# LogicPCB.net
KiCad netlist of a schematic drawn in EAGLE
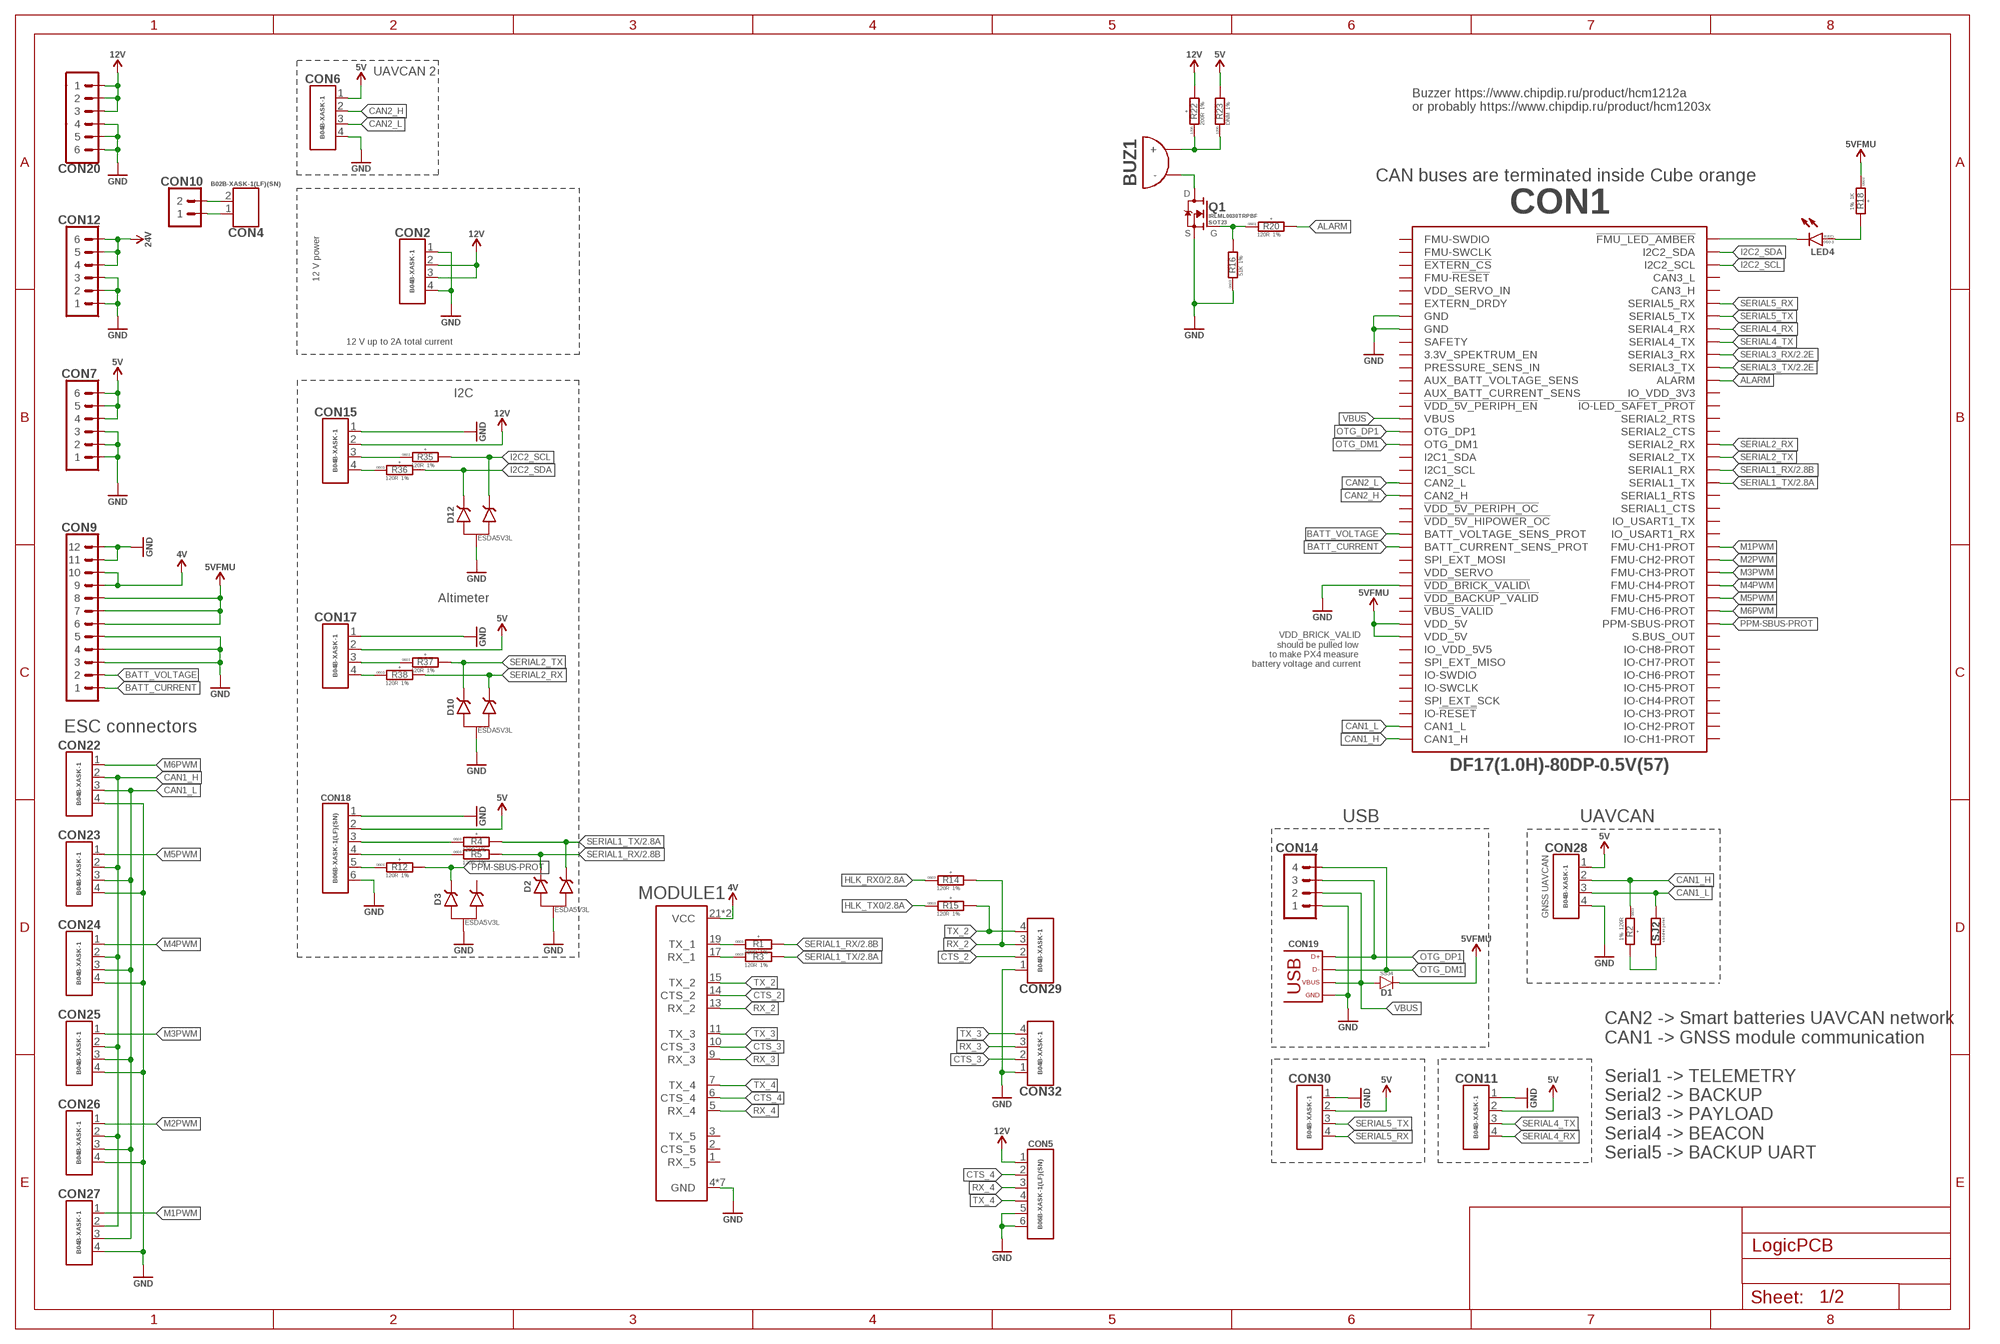
[diagram p0: schematic, sheet 1]
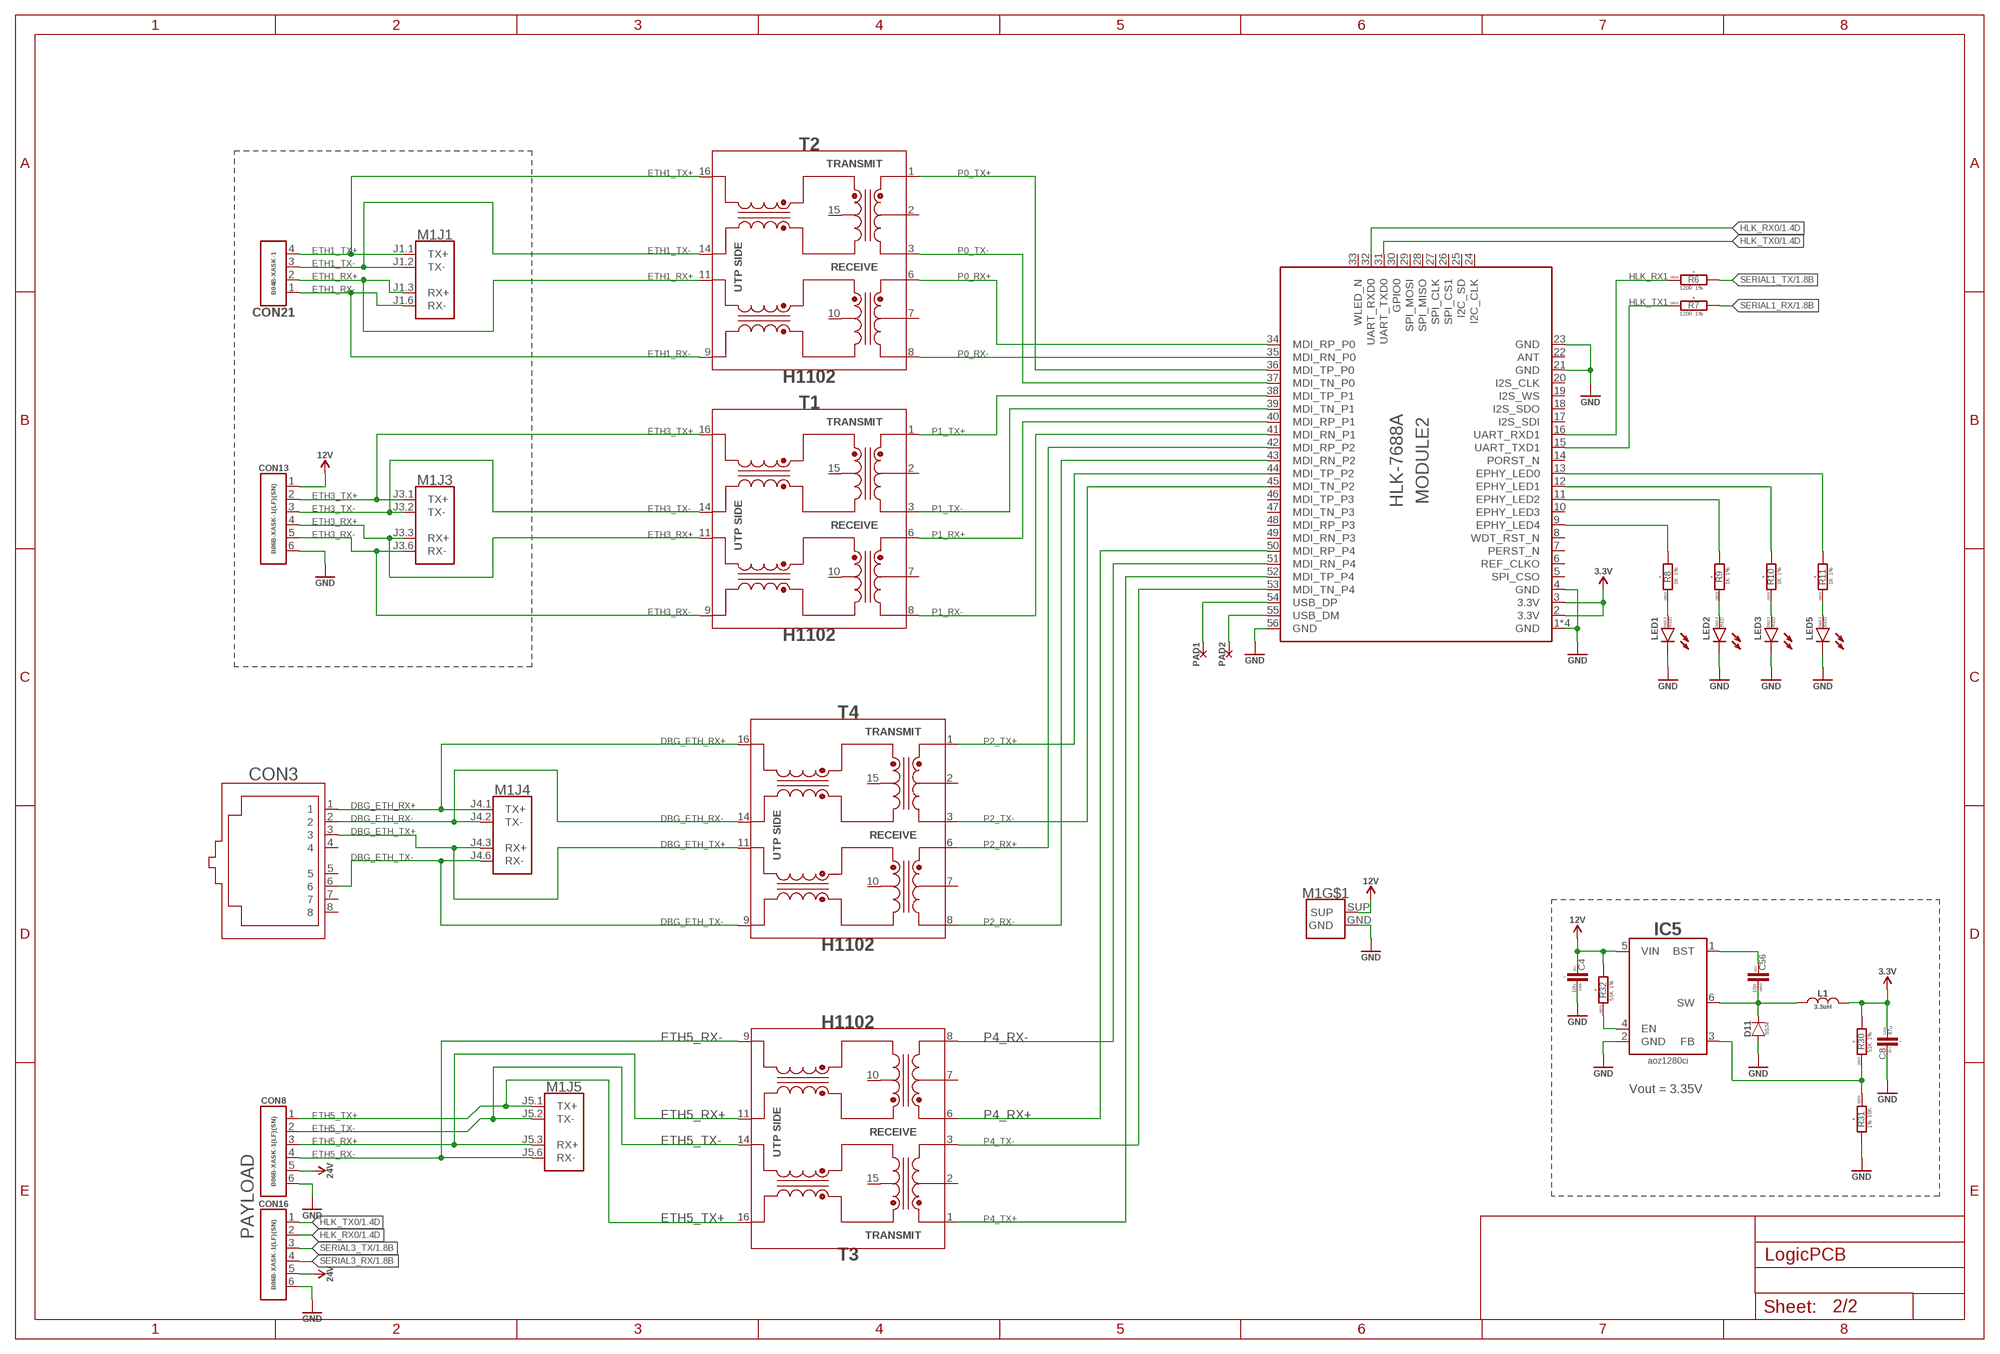
[diagram p1: schematic, sheet 2]

(export (version "E")
  (design (tool "Eeschema 10.0.6"))
  (components
    (comp (ref "C4")
      (value "10u")
      (footprint "eagle-import:C1206")
      (fields
        (field (name "PACKAGE") "1206")
        (field (name "ALLOCATED") "+")
        (field (name "LCSC#") "C77090")
        (field (name "MANF") "Murata Electronics")
        (field (name "MANF#") "GRM31CR61E106KA12L")
        (field (name "OPERATING_TEMP") "-55 to 85 ℃")
        (field (name "VOLTAGE") "25V")
      )
      (libsource (lib "eagle-import") (part "C-1206"))
    )
    (comp (ref "C8")
      (value "47u")
      (footprint "eagle-import:C1206")
      (fields
        (field (name "PACKAGE") "1206")
        (field (name "ALLOCATED") "+")
        (field (name "LCSC#") "C403725")
        (field (name "MANF") "Murata Electronics")
        (field (name "MANF#") "GRM31CR61E476ME44L")
        (field (name "VOLTAGE") "25V")
      )
      (libsource (lib "eagle-import") (part "C-1206"))
    )
    (comp (ref "C56")
      (value "10n")
      (footprint "eagle-import:C0603")
      (fields (field (name "PACKAGE") "0603") (field (name "VOLTAGE") "50V"))
      (libsource (lib "eagle-import") (part "C-0603"))
    )
    (comp (ref "CON3")
      (value "RJ45-NO_SHIELD-5556416-1")
      (footprint "eagle-import:5556416-1")
      (fields (field (name "MANF") "TE Connectivity"))
      (libsource (lib "eagle-import") (part "RJ45-NO_SHIELD-5556416-1"))
    )
    (comp (ref "CON8")
      (value "CON-6P-JST-XA")
      (footprint "eagle-import:B06B-XASK-1")
      (fields (field (name "MANF#") "B06B-XASK-1(LF)(SN)") (field (name "MANF") "JST Sales America"))
      (libsource (lib "eagle-import") (part "CON-6P-JST-XA"))
    )
    (comp (ref "CON13")
      (value "CON-6P-JST-XA")
      (footprint "eagle-import:B06B-XASK-1")
      (fields (field (name "MANF#") "B06B-XASK-1(LF)(SN)") (field (name "MANF") "JST Sales America"))
      (libsource (lib "eagle-import") (part "CON-6P-JST-XA"))
    )
    (comp (ref "CON16")
      (value "CON-6P-JST-XA")
      (footprint "eagle-import:B06B-XASK-1")
      (fields (field (name "MANF#") "B06B-XASK-1(LF)(SN)") (field (name "MANF") "JST Sales America"))
      (libsource (lib "eagle-import") (part "CON-6P-JST-XA"))
    )
    (comp (ref "CON21")
      (value "CON-4P-JST-XA")
      (footprint "eagle-import:B04B-XASK-1")
      (fields (field (name "MANF#") "B04B-XASK-1") (field (name "MANF") "JST Sales America"))
      (libsource (lib "eagle-import") (part "CON-4P-JST-XA"))
    )
    (comp (ref "D11")
      (value "SS34")
      (footprint "eagle-import:DO-214AC(SMA)")
      (fields (field (name "MANF#") "SS34") (field (name "MANF") "MDD（Microdiode Electronics）"))
      (libsource (lib "eagle-import") (part "SS34"))
    )
    (comp (ref "IC5")
      (value "AOZ1280")
      (footprint "eagle-import:SOT23-6")
      (fields (field (name "MANF#") "aoz1280ci") (field (name "MANF") "Alpha & Omega Semicon"))
      (libsource (lib "eagle-import") (part "AOZ1280"))
    )
    (comp (ref "L1")
      (value "3.3uH")
      (footprint "eagle-import:IHLP-2020BZ-01")
      (fields (field (name "MANF") "Vishay Precision Group"))
      (libsource (lib "eagle-import") (part "3.3µH-IHLP-202BZ"))
    )
    (comp (ref "LED1")
      (value "LED-0603")
      (footprint "eagle-import:LED0603")
      (fields
        (field (name "PACKAGE") "0603")
        (field (name "COLOR") "RED")
        (field (name "LCSC#") "C2286")
        (field (name "MANF") "Hubei KENTO Elec")
        (field (name "MANF#") "KT-0603R")
      )
      (libsource (lib "eagle-import") (part "LED-0603"))
    )
    (comp (ref "LED2")
      (value "LED-0603")
      (footprint "eagle-import:LED0603")
      (fields
        (field (name "PACKAGE") "0603")
        (field (name "COLOR") "RED")
        (field (name "LCSC#") "C2286")
        (field (name "MANF") "Hubei KENTO Elec")
        (field (name "MANF#") "KT-0603R")
      )
      (libsource (lib "eagle-import") (part "LED-0603"))
    )
    (comp (ref "LED3")
      (value "LED-0603")
      (footprint "eagle-import:LED0603")
      (fields
        (field (name "PACKAGE") "0603")
        (field (name "COLOR") "RED")
        (field (name "LCSC#") "C2286")
        (field (name "MANF") "Hubei KENTO Elec")
        (field (name "MANF#") "KT-0603R")
      )
      (libsource (lib "eagle-import") (part "LED-0603"))
    )
    (comp (ref "LED5")
      (value "LED-0603")
      (footprint "eagle-import:LED0603")
      (fields
        (field (name "PACKAGE") "0603")
        (field (name "COLOR") "RED")
        (field (name "LCSC#") "C2286")
        (field (name "MANF") "Hubei KENTO Elec")
        (field (name "MANF#") "KT-0603R")
      )
      (libsource (lib "eagle-import") (part "LED-0603"))
    )
    (comp (ref "M1")
      (value "05G_ETHERNET_SWITCH")
      (footprint "eagle-import:05G_ETH_SWITCH")
      (libsource (lib "eagle-import") (part "05G_ETHERNET_SWITCH"))
    )
    (comp (ref "MODULE2")
      (value "HLK-7688A")
      (footprint "eagle-import:HLK-7688A")
      (fields (field (name "MANF") "Hi-link"))
      (libsource (lib "eagle-import") (part "HLK-7688A"))
    )
    (comp (ref "PAD1")
      (value "PAD-HEX-2MM")
      (footprint "eagle-import:HEX-2MM")
      (libsource (lib "eagle-import") (part "PAD-HEX-2MM"))
    )
    (comp (ref "PAD2")
      (value "PAD-HEX-2MM")
      (footprint "eagle-import:HEX-2MM")
      (libsource (lib "eagle-import") (part "PAD-HEX-2MM"))
    )
    (comp (ref "R6")
      (value "120R")
      (footprint "eagle-import:R0603")
      (fields
        (field (name "PACKAGE") "0603")
        (field (name "TOLERANCE") "1%")
        (field (name "ALLOCATED") "+")
        (field (name "LCSC#") "C22787")
        (field (name "MANF") "UNI-ROYAL(Uniroyal Elec)")
        (field (name "MANF#") "0603WAF1200T5E")
      )
      (libsource (lib "eagle-import") (part "R-0603-1%"))
    )
    (comp (ref "R7")
      (value "120R")
      (footprint "eagle-import:R0603")
      (fields
        (field (name "PACKAGE") "0603")
        (field (name "TOLERANCE") "1%")
        (field (name "ALLOCATED") "+")
        (field (name "LCSC#") "C22787")
        (field (name "MANF") "UNI-ROYAL(Uniroyal Elec)")
        (field (name "MANF#") "0603WAF1200T5E")
      )
      (libsource (lib "eagle-import") (part "R-0603-1%"))
    )
    (comp (ref "R8")
      (value "1K")
      (footprint "eagle-import:R0603")
      (fields
        (field (name "PACKAGE") "0603")
        (field (name "TOLERANCE") "1%")
        (field (name "ALLOCATED") "+")
        (field (name "LCSC#") "C21190")
        (field (name "MANF") "UNI-ROYAL(Uniroyal Elec)")
        (field (name "MANF#") "0603WAF1001T5E")
      )
      (libsource (lib "eagle-import") (part "R-0603-1%"))
    )
    (comp (ref "R9")
      (value "1K")
      (footprint "eagle-import:R0603")
      (fields
        (field (name "PACKAGE") "0603")
        (field (name "TOLERANCE") "1%")
        (field (name "ALLOCATED") "+")
        (field (name "LCSC#") "C21190")
        (field (name "MANF") "UNI-ROYAL(Uniroyal Elec)")
        (field (name "MANF#") "0603WAF1001T5E")
      )
      (libsource (lib "eagle-import") (part "R-0603-1%"))
    )
    (comp (ref "R10")
      (value "1K")
      (footprint "eagle-import:R0603")
      (fields
        (field (name "PACKAGE") "0603")
        (field (name "TOLERANCE") "1%")
        (field (name "ALLOCATED") "+")
        (field (name "LCSC#") "C21190")
        (field (name "MANF") "UNI-ROYAL(Uniroyal Elec)")
        (field (name "MANF#") "0603WAF1001T5E")
      )
      (libsource (lib "eagle-import") (part "R-0603-1%"))
    )
    (comp (ref "R11")
      (value "1K")
      (footprint "eagle-import:R0603")
      (fields
        (field (name "PACKAGE") "0603")
        (field (name "TOLERANCE") "1%")
        (field (name "ALLOCATED") "+")
        (field (name "LCSC#") "C21190")
        (field (name "MANF") "UNI-ROYAL(Uniroyal Elec)")
        (field (name "MANF#") "0603WAF1001T5E")
      )
      (libsource (lib "eagle-import") (part "R-0603-1%"))
    )
    (comp (ref "R30")
      (value "51K")
      (footprint "eagle-import:R0603")
      (fields (field (name "PACKAGE") "0603") (field (name "TOLERANCE") "1%") (field (name "ALLOCATED") "+"))
      (libsource (lib "eagle-import") (part "R-0603-1%"))
    )
    (comp (ref "R31")
      (value "16K")
      (footprint "eagle-import:R0603")
      (fields (field (name "PACKAGE") "0603") (field (name "TOLERANCE") "1%") (field (name "ALLOCATED") "+"))
      (libsource (lib "eagle-import") (part "R-0603-1%"))
    )
    (comp (ref "R32")
      (value "51K")
      (footprint "eagle-import:R0603")
      (fields (field (name "PACKAGE") "0603") (field (name "TOLERANCE") "1%") (field (name "ALLOCATED") "+"))
      (libsource (lib "eagle-import") (part "R-0603-1%"))
    )
    (comp (ref "T1")
      (value "H1102NL")
      (footprint "eagle-import:H1102")
      (fields (field (name "MANF") "Pulse Electronics Corporation"))
      (libsource (lib "eagle-import") (part "H1102NL"))
    )
    (comp (ref "T2")
      (value "H1102NL")
      (footprint "eagle-import:H1102")
      (fields (field (name "MANF") "Pulse Electronics Corporation"))
      (libsource (lib "eagle-import") (part "H1102NL"))
    )
    (comp (ref "T3")
      (value "H1102NL")
      (footprint "eagle-import:H1102")
      (fields (field (name "MANF") "Pulse Electronics Corporation"))
      (libsource (lib "eagle-import") (part "H1102NL"))
    )
    (comp (ref "T4")
      (value "H1102NL")
      (footprint "eagle-import:H1102")
      (fields (field (name "MANF") "Pulse Electronics Corporation"))
      (libsource (lib "eagle-import") (part "H1102NL"))
    )
    (comp (ref "BUZ1")
      (value "BUZZER-ЕР-12MM")
      (footprint "eagle-import:BUZZER_12MM")
      (fields (field (name "MANF") "JL World") (field (name "MANF#") "HCM1212A"))
      (libsource (lib "eagle-import") (part "BUZZER-ЕР-12MM"))
    )
    (comp (ref "CON1")
      (value "CUBE_ORANGE_")
      (footprint "eagle-import:CUBE_ORANGE")
      (fields (field (name "MANF#") "DF17(1.0H)-80DP-0.5V(57)") (field (name "MANF") "HIROSE"))
      (libsource (lib "eagle-import") (part "CUBE_ORANGE_"))
    )
    (comp (ref "CON2")
      (value "CON-4P-JST-XA")
      (footprint "eagle-import:B04B-XASK-1")
      (fields (field (name "MANF#") "B04B-XASK-1") (field (name "MANF") "JST Sales America"))
      (libsource (lib "eagle-import") (part "CON-4P-JST-XA"))
    )
    (comp (ref "CON4")
      (value "CON-2P-JST-XA")
      (footprint "eagle-import:B02B-XASK-1")
      (fields (field (name "MANF#") "B02B-XASK-1(LF)(SN)") (field (name "MANF") "JST Sales America"))
      (libsource (lib "eagle-import") (part "CON-2P-JST-XA"))
    )
    (comp (ref "CON5")
      (value "CON-6P-JST-XA")
      (footprint "eagle-import:B06B-XASK-1")
      (fields (field (name "MANF#") "B06B-XASK-1(LF)(SN)") (field (name "MANF") "JST Sales America"))
      (libsource (lib "eagle-import") (part "CON-6P-JST-XA"))
    )
    (comp (ref "CON6")
      (value "CON-4P-JST-XA")
      (footprint "eagle-import:B04B-XASK-1")
      (fields (field (name "MANF#") "B04B-XASK-1") (field (name "MANF") "JST Sales America"))
      (libsource (lib "eagle-import") (part "CON-4P-JST-XA"))
    )
    (comp (ref "CON7")
      (value "PINHEAD_1X06-2.54")
      (footprint "eagle-import:1X06-PTH-2.54")
      (libsource (lib "eagle-import") (part "PINHEAD_1X06-2.54"))
    )
    (comp (ref "CON9")
      (value "PINHEAD_1X12-2.54")
      (footprint "eagle-import:1X12-PTH-2.54")
      (libsource (lib "eagle-import") (part "PINHEAD_1X12-2.54"))
    )
    (comp (ref "CON10")
      (value "PINHEAD_1X02-2.54")
      (footprint "eagle-import:1X02-PTH-2.54")
      (libsource (lib "eagle-import") (part "PINHEAD_1X02-2.54"))
    )
    (comp (ref "CON11")
      (value "CON-4P-JST-XA")
      (footprint "eagle-import:B04B-XASK-1")
      (fields (field (name "MANF#") "B04B-XASK-1") (field (name "MANF") "JST Sales America"))
      (libsource (lib "eagle-import") (part "CON-4P-JST-XA"))
    )
    (comp (ref "CON12")
      (value "PINHEAD_1X06-2.54")
      (footprint "eagle-import:1X06-PTH-2.54")
      (libsource (lib "eagle-import") (part "PINHEAD_1X06-2.54"))
    )
    (comp (ref "CON14")
      (value "PINHEAD_1X04-2.54")
      (footprint "eagle-import:1X04-PTH-2.54")
      (libsource (lib "eagle-import") (part "PINHEAD_1X04-2.54"))
    )
    (comp (ref "CON15")
      (value "CON-4P-JST-XA")
      (footprint "eagle-import:B04B-XASK-1")
      (fields (field (name "MANF#") "B04B-XASK-1") (field (name "MANF") "JST Sales America"))
      (libsource (lib "eagle-import") (part "CON-4P-JST-XA"))
    )
    (comp (ref "CON17")
      (value "CON-4P-JST-XA")
      (footprint "eagle-import:B04B-XASK-1")
      (fields (field (name "MANF#") "B04B-XASK-1") (field (name "MANF") "JST Sales America"))
      (libsource (lib "eagle-import") (part "CON-4P-JST-XA"))
    )
    (comp (ref "CON18")
      (value "CON-6P-JST-XA")
      (footprint "eagle-import:B06B-XASK-1")
      (fields (field (name "MANF#") "B06B-XASK-1(LF)(SN)") (field (name "MANF") "JST Sales America"))
      (libsource (lib "eagle-import") (part "CON-6P-JST-XA"))
    )
    (comp (ref "CON19")
      (value "USB-TYPE-C-VERT-PROD")
      (footprint "eagle-import:2047110001-PROD")
      (fields (field (name "MANF") "Molex"))
      (libsource (lib "eagle-import") (part "USB-TYPE-C-VERT-PROD"))
    )
    (comp (ref "CON20")
      (value "PINHEAD_1X06-2.54")
      (footprint "eagle-import:1X06-PTH-2.54")
      (libsource (lib "eagle-import") (part "PINHEAD_1X06-2.54"))
    )
    (comp (ref "CON22")
      (value "CON-4P-JST-XA")
      (footprint "eagle-import:B04B-XASK-1")
      (fields (field (name "MANF#") "B04B-XASK-1") (field (name "MANF") "JST Sales America"))
      (libsource (lib "eagle-import") (part "CON-4P-JST-XA"))
    )
    (comp (ref "CON23")
      (value "CON-4P-JST-XA")
      (footprint "eagle-import:B04B-XASK-1")
      (fields (field (name "MANF#") "B04B-XASK-1") (field (name "MANF") "JST Sales America"))
      (libsource (lib "eagle-import") (part "CON-4P-JST-XA"))
    )
    (comp (ref "CON24")
      (value "CON-4P-JST-XA")
      (footprint "eagle-import:B04B-XASK-1")
      (fields (field (name "MANF#") "B04B-XASK-1") (field (name "MANF") "JST Sales America"))
      (libsource (lib "eagle-import") (part "CON-4P-JST-XA"))
    )
    (comp (ref "CON25")
      (value "CON-4P-JST-XA")
      (footprint "eagle-import:B04B-XASK-1")
      (fields (field (name "MANF#") "B04B-XASK-1") (field (name "MANF") "JST Sales America"))
      (libsource (lib "eagle-import") (part "CON-4P-JST-XA"))
    )
    (comp (ref "CON26")
      (value "CON-4P-JST-XA")
      (footprint "eagle-import:B04B-XASK-1")
      (fields (field (name "MANF#") "B04B-XASK-1") (field (name "MANF") "JST Sales America"))
      (libsource (lib "eagle-import") (part "CON-4P-JST-XA"))
    )
    (comp (ref "CON27")
      (value "CON-4P-JST-XA")
      (footprint "eagle-import:B04B-XASK-1")
      (fields (field (name "MANF#") "B04B-XASK-1") (field (name "MANF") "JST Sales America"))
      (libsource (lib "eagle-import") (part "CON-4P-JST-XA"))
    )
    (comp (ref "CON28")
      (value "CON-4P-JST-XA")
      (footprint "eagle-import:B04B-XASK-1")
      (fields (field (name "MANF#") "B04B-XASK-1") (field (name "MANF") "JST Sales America"))
      (libsource (lib "eagle-import") (part "CON-4P-JST-XA"))
    )
    (comp (ref "CON29")
      (value "CON-4P-JST-XA")
      (footprint "eagle-import:B04B-XASK-1")
      (fields (field (name "MANF#") "B04B-XASK-1") (field (name "MANF") "JST Sales America"))
      (libsource (lib "eagle-import") (part "CON-4P-JST-XA"))
    )
    (comp (ref "CON30")
      (value "CON-4P-JST-XA")
      (footprint "eagle-import:B04B-XASK-1")
      (fields (field (name "MANF#") "B04B-XASK-1") (field (name "MANF") "JST Sales America"))
      (libsource (lib "eagle-import") (part "CON-4P-JST-XA"))
    )
    (comp (ref "CON32")
      (value "CON-4P-JST-XA")
      (footprint "eagle-import:B04B-XASK-1")
      (fields (field (name "MANF#") "B04B-XASK-1") (field (name "MANF") "JST Sales America"))
      (libsource (lib "eagle-import") (part "CON-4P-JST-XA"))
    )
    (comp (ref "D1")
      (value "SS34")
      (footprint "eagle-import:DO-214AC(SMA)")
      (fields (field (name "MANF#") "SS34") (field (name "MANF") "MDD（Microdiode Electronics）"))
      (libsource (lib "eagle-import") (part "SS34"))
    )
    (comp (ref "D2")
      (value "ESDA5V3L")
      (footprint "eagle-import:SOT23B-3")
      (fields (field (name "MANF#") "ESDA5V3L") (field (name "MANF") "STMicroelectronics"))
      (libsource (lib "eagle-import") (part "ESDA5V3L"))
    )
    (comp (ref "D3")
      (value "ESDA5V3L")
      (footprint "eagle-import:SOT23B-3")
      (fields (field (name "MANF#") "ESDA5V3L") (field (name "MANF") "STMicroelectronics"))
      (libsource (lib "eagle-import") (part "ESDA5V3L"))
    )
    (comp (ref "D10")
      (value "ESDA5V3L")
      (footprint "eagle-import:SOT23B-3")
      (fields (field (name "MANF#") "ESDA5V3L") (field (name "MANF") "STMicroelectronics"))
      (libsource (lib "eagle-import") (part "ESDA5V3L"))
    )
    (comp (ref "D12")
      (value "ESDA5V3L")
      (footprint "eagle-import:SOT23B-3")
      (fields (field (name "MANF#") "ESDA5V3L") (field (name "MANF") "STMicroelectronics"))
      (libsource (lib "eagle-import") (part "ESDA5V3L"))
    )
    (comp (ref "LED4")
      (value "LED-0603")
      (footprint "eagle-import:LED0603")
      (fields
        (field (name "PACKAGE") "0603")
        (field (name "COLOR") "RED")
        (field (name "LCSC#") "C2286")
        (field (name "MANF") "Hubei KENTO Elec")
        (field (name "MANF#") "KT-0603R")
      )
      (libsource (lib "eagle-import") (part "LED-0603"))
    )
    (comp (ref "MODULE1")
      (value "MODEM_CARRIER")
      (footprint "eagle-import:MODEM_CARRIER")
      (libsource (lib "eagle-import") (part "MODEM_CARRIER"))
    )
    (comp (ref "Q1")
      (value "IRLML0030")
      (footprint "eagle-import:SOT23")
      (fields
        (field (name "MANF#") "IRLML0030TRPBF")
        (field (name "PACKAGE") "SOT23")
        (field (name "MANF") "Infineon Technologies")
      )
      (libsource (lib "eagle-import") (part "IRLML0030"))
    )
    (comp (ref "R1")
      (value "120R")
      (footprint "eagle-import:R0603")
      (fields
        (field (name "PACKAGE") "0603")
        (field (name "TOLERANCE") "1%")
        (field (name "ALLOCATED") "+")
        (field (name "LCSC#") "C22787")
        (field (name "MANF") "UNI-ROYAL(Uniroyal Elec)")
        (field (name "MANF#") "0603WAF1200T5E")
      )
      (libsource (lib "eagle-import") (part "R-0603-1%"))
    )
    (comp (ref "R2")
      (value "120R")
      (footprint "eagle-import:R0603")
      (fields
        (field (name "PACKAGE") "0603")
        (field (name "TOLERANCE") "1%")
        (field (name "ALLOCATED") "+")
        (field (name "LCSC#") "C22787")
        (field (name "MANF") "UNI-ROYAL(Uniroyal Elec)")
        (field (name "MANF#") "0603WAF1200T5E")
      )
      (libsource (lib "eagle-import") (part "R-0603-1%"))
    )
    (comp (ref "R3")
      (value "120R")
      (footprint "eagle-import:R0603")
      (fields
        (field (name "PACKAGE") "0603")
        (field (name "TOLERANCE") "1%")
        (field (name "ALLOCATED") "+")
        (field (name "LCSC#") "C22787")
        (field (name "MANF") "UNI-ROYAL(Uniroyal Elec)")
        (field (name "MANF#") "0603WAF1200T5E")
      )
      (libsource (lib "eagle-import") (part "R-0603-1%"))
    )
    (comp (ref "R4")
      (value "120R")
      (footprint "eagle-import:R0603")
      (fields
        (field (name "PACKAGE") "0603")
        (field (name "TOLERANCE") "1%")
        (field (name "ALLOCATED") "+")
        (field (name "LCSC#") "C22787")
        (field (name "MANF") "UNI-ROYAL(Uniroyal Elec)")
        (field (name "MANF#") "0603WAF1200T5E")
      )
      (libsource (lib "eagle-import") (part "R-0603-1%"))
    )
    (comp (ref "R5")
      (value "120R")
      (footprint "eagle-import:R0603")
      (fields
        (field (name "PACKAGE") "0603")
        (field (name "TOLERANCE") "1%")
        (field (name "ALLOCATED") "+")
        (field (name "LCSC#") "C22787")
        (field (name "MANF") "UNI-ROYAL(Uniroyal Elec)")
        (field (name "MANF#") "0603WAF1200T5E")
      )
      (libsource (lib "eagle-import") (part "R-0603-1%"))
    )
    (comp (ref "R12")
      (value "120R")
      (footprint "eagle-import:R0603")
      (fields
        (field (name "PACKAGE") "0603")
        (field (name "TOLERANCE") "1%")
        (field (name "ALLOCATED") "+")
        (field (name "LCSC#") "C22787")
        (field (name "MANF") "UNI-ROYAL(Uniroyal Elec)")
        (field (name "MANF#") "0603WAF1200T5E")
      )
      (libsource (lib "eagle-import") (part "R-0603-1%"))
    )
    (comp (ref "R14")
      (value "120R")
      (footprint "eagle-import:R0603")
      (fields
        (field (name "PACKAGE") "0603")
        (field (name "TOLERANCE") "1%")
        (field (name "ALLOCATED") "+")
        (field (name "LCSC#") "C22787")
        (field (name "MANF") "UNI-ROYAL(Uniroyal Elec)")
        (field (name "MANF#") "0603WAF1200T5E")
      )
      (libsource (lib "eagle-import") (part "R-0603-1%"))
    )
    (comp (ref "R15")
      (value "120R")
      (footprint "eagle-import:R0603")
      (fields
        (field (name "PACKAGE") "0603")
        (field (name "TOLERANCE") "1%")
        (field (name "ALLOCATED") "+")
        (field (name "LCSC#") "C22787")
        (field (name "MANF") "UNI-ROYAL(Uniroyal Elec)")
        (field (name "MANF#") "0603WAF1200T5E")
      )
      (libsource (lib "eagle-import") (part "R-0603-1%"))
    )
    (comp (ref "R16")
      (value "51K")
      (footprint "eagle-import:R0603")
      (fields (field (name "PACKAGE") "0603") (field (name "TOLERANCE") "1%") (field (name "LCSC#") "C23196"))
      (libsource (lib "eagle-import") (part "R-0603-1%"))
    )
    (comp (ref "R18")
      (value "1K")
      (footprint "eagle-import:R0603")
      (fields
        (field (name "PACKAGE") "0603")
        (field (name "TOLERANCE") "1%")
        (field (name "ALLOCATED") "+")
        (field (name "LCSC#") "C21190")
        (field (name "MANF") "UNI-ROYAL(Uniroyal Elec)")
        (field (name "MANF#") "0603WAF1001T5E")
      )
      (libsource (lib "eagle-import") (part "R-0603-1%"))
    )
    (comp (ref "R20")
      (value "120R")
      (footprint "eagle-import:R0603")
      (fields
        (field (name "PACKAGE") "0603")
        (field (name "TOLERANCE") "1%")
        (field (name "ALLOCATED") "+")
        (field (name "LCSC#") "C22787")
        (field (name "MANF") "UNI-ROYAL(Uniroyal Elec)")
        (field (name "MANF#") "0603WAF1200T5E")
      )
      (libsource (lib "eagle-import") (part "R-0603-1%"))
    )
    (comp (ref "R22")
      (value "200R")
      (footprint "eagle-import:R1206")
      (fields
        (field (name "PACKAGE") "1206")
        (field (name "TOLERANCE") "1%")
        (field (name "ALLOCATED") "+")
        (field (name "LCSC#") "C25361")
        (field (name "MANF") "UNI-ROYAL")
        (field (name "MANF#") "1206W4J0201T5E")
      )
      (libsource (lib "eagle-import") (part "R-1206-1%"))
    )
    (comp (ref "R23")
      (value "DNM")
      (footprint "eagle-import:R1206")
      (fields (field (name "PACKAGE") "1206") (field (name "TOLERANCE") "1%"))
      (libsource (lib "eagle-import") (part "R-1206-1%"))
    )
    (comp (ref "R35")
      (value "120R")
      (footprint "eagle-import:R0603")
      (fields
        (field (name "PACKAGE") "0603")
        (field (name "TOLERANCE") "1%")
        (field (name "ALLOCATED") "+")
        (field (name "LCSC#") "C22787")
        (field (name "MANF") "UNI-ROYAL(Uniroyal Elec)")
        (field (name "MANF#") "0603WAF1200T5E")
      )
      (libsource (lib "eagle-import") (part "R-0603-1%"))
    )
    (comp (ref "R36")
      (value "120R")
      (footprint "eagle-import:R0603")
      (fields
        (field (name "PACKAGE") "0603")
        (field (name "TOLERANCE") "1%")
        (field (name "ALLOCATED") "+")
        (field (name "LCSC#") "C22787")
        (field (name "MANF") "UNI-ROYAL(Uniroyal Elec)")
        (field (name "MANF#") "0603WAF1200T5E")
      )
      (libsource (lib "eagle-import") (part "R-0603-1%"))
    )
    (comp (ref "R37")
      (value "120R")
      (footprint "eagle-import:R0603")
      (fields
        (field (name "PACKAGE") "0603")
        (field (name "TOLERANCE") "1%")
        (field (name "ALLOCATED") "+")
        (field (name "LCSC#") "C22787")
        (field (name "MANF") "UNI-ROYAL(Uniroyal Elec)")
        (field (name "MANF#") "0603WAF1200T5E")
      )
      (libsource (lib "eagle-import") (part "R-0603-1%"))
    )
    (comp (ref "R38")
      (value "120R")
      (footprint "eagle-import:R0603")
      (fields
        (field (name "PACKAGE") "0603")
        (field (name "TOLERANCE") "1%")
        (field (name "ALLOCATED") "+")
        (field (name "LCSC#") "C22787")
        (field (name "MANF") "UNI-ROYAL(Uniroyal Elec)")
        (field (name "MANF#") "0603WAF1200T5E")
      )
      (libsource (lib "eagle-import") (part "R-0603-1%"))
    )
    (comp (ref "SJ2")
      (value "SOLDER_JOINT-SJ1")
      (footprint "eagle-import:RES_0")
      (libsource (lib "eagle-import") (part "SOLDER_JOINT-SJ1"))
    )
  )
  (nets
    (net (code "1") (name "5VFMU") (class "Default")
      (node (ref "CON1") (pin "61") (pinfunction "VDD_5V_61") (pintype "bidirectional"))
      (node (ref "CON1") (pin "63") (pinfunction "VDD_5V_63") (pintype "bidirectional"))
      (node (ref "CON9") (pin "6") (pinfunction "6_6") (pintype "passive"))
      (node (ref "CON9") (pin "7") (pinfunction "7_7") (pintype "passive"))
      (node (ref "CON9") (pin "8") (pinfunction "8_8") (pintype "passive"))
      (node (ref "D1") (pin "C") (pinfunction "C_C") (pintype "passive"))
      (node (ref "R18") (pin "1") (pinfunction "1_1") (pintype "passive"))
    )
    (net (code "2") (name "8") (class "Default")
      (node (ref "CON3") (pin "8") (pinfunction "8_8") (pintype "power_in"))
    )
    (net (code "3") (name "ALARM") (class "Default")
      (node (ref "CON1") (pin "24") (pinfunction "ALARM_24") (pintype "bidirectional"))
      (node (ref "R20") (pin "2") (pinfunction "2_2") (pintype "passive"))
    )
    (net (code "4") (name "BATT_CURRENT") (class "Default")
      (node (ref "CON1") (pin "49") (pinfunction "BATT_CURRENT_SENS_PROT_49") (pintype "bidirectional"))
      (node (ref "CON9") (pin "1") (pinfunction "1_1") (pintype "passive"))
    )
    (net (code "5") (name "BATT_VOLTAGE") (class "Default")
      (node (ref "CON1") (pin "47") (pinfunction "BATT_VOLTAGE_SENS_PROT_47") (pintype "bidirectional"))
      (node (ref "CON9") (pin "2") (pinfunction "2_2") (pintype "passive"))
    )
    (net (code "6") (name "CAN1_H") (class "Default")
      (node (ref "CON1") (pin "79") (pinfunction "CAN1_H_79") (pintype "bidirectional"))
      (node (ref "CON22") (pin "2") (pinfunction "2_2") (pintype "bidirectional"))
      (node (ref "CON23") (pin "2") (pinfunction "2_2") (pintype "bidirectional"))
      (node (ref "CON24") (pin "2") (pinfunction "2_2") (pintype "bidirectional"))
      (node (ref "CON25") (pin "2") (pinfunction "2_2") (pintype "bidirectional"))
      (node (ref "CON26") (pin "2") (pinfunction "2_2") (pintype "bidirectional"))
      (node (ref "CON27") (pin "2") (pinfunction "2_2") (pintype "bidirectional"))
      (node (ref "CON28") (pin "2") (pinfunction "2_2") (pintype "bidirectional"))
      (node (ref "R2") (pin "1") (pinfunction "1_1") (pintype "passive"))
    )
    (net (code "7") (name "CAN1_L") (class "Default")
      (node (ref "CON1") (pin "77") (pinfunction "CAN1_L_77") (pintype "bidirectional"))
      (node (ref "CON22") (pin "3") (pinfunction "3_3") (pintype "bidirectional"))
      (node (ref "CON23") (pin "3") (pinfunction "3_3") (pintype "bidirectional"))
      (node (ref "CON24") (pin "3") (pinfunction "3_3") (pintype "bidirectional"))
      (node (ref "CON25") (pin "3") (pinfunction "3_3") (pintype "bidirectional"))
      (node (ref "CON26") (pin "3") (pinfunction "3_3") (pintype "bidirectional"))
      (node (ref "CON27") (pin "3") (pinfunction "3_3") (pintype "bidirectional"))
      (node (ref "CON28") (pin "3") (pinfunction "3_3") (pintype "bidirectional"))
      (node (ref "SJ2") (pin "2") (pinfunction "2_2") (pintype "passive"))
    )
    (net (code "8") (name "CAN2_H") (class "Default")
      (node (ref "CON1") (pin "41") (pinfunction "CAN2_H_41") (pintype "bidirectional"))
      (node (ref "CON6") (pin "2") (pinfunction "2_2") (pintype "bidirectional"))
    )
    (net (code "9") (name "CAN2_L") (class "Default")
      (node (ref "CON1") (pin "39") (pinfunction "CAN2_L_39") (pintype "bidirectional"))
      (node (ref "CON6") (pin "3") (pinfunction "3_3") (pintype "bidirectional"))
    )
    (net (code "10") (name "CTS_2") (class "Default")
      (node (ref "CON29") (pin "2") (pinfunction "2_2") (pintype "bidirectional"))
      (node (ref "MODULE1") (pin "14") (pinfunction "CTS_2_14") (pintype "bidirectional"))
    )
    (net (code "11") (name "CTS_3") (class "Default")
      (node (ref "CON32") (pin "2") (pinfunction "2_2") (pintype "bidirectional"))
      (node (ref "MODULE1") (pin "10") (pinfunction "CTS_3_10") (pintype "bidirectional"))
    )
    (net (code "12") (name "CTS_4") (class "Default")
      (node (ref "CON5") (pin "2") (pinfunction "2_2") (pintype "bidirectional"))
      (node (ref "MODULE1") (pin "6") (pinfunction "CTS_4_6") (pintype "bidirectional"))
    )
    (net (code "13") (name "DBG_ETH_RX+") (class "Default")
      (node (ref "CON3") (pin "1") (pinfunction "1_1") (pintype "bidirectional"))
      (node (ref "M1") (pin "J4.1") (pinfunction "TX+_J4.1") (pintype "bidirectional"))
      (node (ref "T4") (pin "16") (pinfunction "16_16") (pintype "bidirectional"))
    )
    (net (code "14") (name "DBG_ETH_RX-") (class "Default")
      (node (ref "CON3") (pin "2") (pinfunction "2_2") (pintype "bidirectional"))
      (node (ref "M1") (pin "J4.2") (pinfunction "TX-_J4.2") (pintype "bidirectional"))
      (node (ref "T4") (pin "14") (pinfunction "14_14") (pintype "bidirectional"))
    )
    (net (code "15") (name "DBG_ETH_TX+") (class "Default")
      (node (ref "CON3") (pin "3") (pinfunction "3_3") (pintype "bidirectional"))
      (node (ref "M1") (pin "J4.3") (pinfunction "RX+_J4.3") (pintype "bidirectional"))
      (node (ref "T4") (pin "11") (pinfunction "11_11") (pintype "bidirectional"))
    )
    (net (code "16") (name "DBG_ETH_TX-") (class "Default")
      (node (ref "CON3") (pin "6") (pinfunction "6_6") (pintype "bidirectional"))
      (node (ref "M1") (pin "J4.6") (pinfunction "RX-_J4.6") (pintype "bidirectional"))
      (node (ref "T4") (pin "9") (pinfunction "9_9") (pintype "bidirectional"))
    )
    (net (code "17") (name "ETH1_RX+") (class "Default")
      (node (ref "CON21") (pin "2") (pinfunction "2_2") (pintype "bidirectional"))
      (node (ref "M1") (pin "J1.3") (pinfunction "RX+_J1.3") (pintype "bidirectional"))
      (node (ref "T2") (pin "11") (pinfunction "11_11") (pintype "bidirectional"))
    )
    (net (code "18") (name "ETH1_RX-") (class "Default")
      (node (ref "CON21") (pin "1") (pinfunction "1_1") (pintype "bidirectional"))
      (node (ref "M1") (pin "J1.6") (pinfunction "RX-_J1.6") (pintype "bidirectional"))
      (node (ref "T2") (pin "9") (pinfunction "9_9") (pintype "bidirectional"))
    )
    (net (code "19") (name "ETH1_TX+") (class "Default")
      (node (ref "CON21") (pin "4") (pinfunction "4_4") (pintype "bidirectional"))
      (node (ref "M1") (pin "J1.1") (pinfunction "TX+_J1.1") (pintype "bidirectional"))
      (node (ref "T2") (pin "16") (pinfunction "16_16") (pintype "bidirectional"))
    )
    (net (code "20") (name "ETH1_TX-") (class "Default")
      (node (ref "CON21") (pin "3") (pinfunction "3_3") (pintype "bidirectional"))
      (node (ref "M1") (pin "J1.2") (pinfunction "TX-_J1.2") (pintype "bidirectional"))
      (node (ref "T2") (pin "14") (pinfunction "14_14") (pintype "bidirectional"))
    )
    (net (code "21") (name "ETH3_RX+") (class "Default")
      (node (ref "CON13") (pin "4") (pinfunction "4_4") (pintype "bidirectional"))
      (node (ref "M1") (pin "J3.3") (pinfunction "RX+_J3.3") (pintype "bidirectional"))
      (node (ref "T1") (pin "11") (pinfunction "11_11") (pintype "bidirectional"))
    )
    (net (code "22") (name "ETH3_RX-") (class "Default")
      (node (ref "CON13") (pin "5") (pinfunction "5_5") (pintype "bidirectional"))
      (node (ref "M1") (pin "J3.6") (pinfunction "RX-_J3.6") (pintype "bidirectional"))
      (node (ref "T1") (pin "9") (pinfunction "9_9") (pintype "bidirectional"))
    )
    (net (code "23") (name "ETH3_TX+") (class "Default")
      (node (ref "CON13") (pin "2") (pinfunction "2_2") (pintype "bidirectional"))
      (node (ref "M1") (pin "J3.1") (pinfunction "TX+_J3.1") (pintype "bidirectional"))
      (node (ref "T1") (pin "16") (pinfunction "16_16") (pintype "bidirectional"))
    )
    (net (code "24") (name "ETH3_TX-") (class "Default")
      (node (ref "CON13") (pin "3") (pinfunction "3_3") (pintype "bidirectional"))
      (node (ref "M1") (pin "J3.2") (pinfunction "TX-_J3.2") (pintype "bidirectional"))
      (node (ref "T1") (pin "14") (pinfunction "14_14") (pintype "bidirectional"))
    )
    (net (code "25") (name "ETH5_RX+") (class "Default")
      (node (ref "CON8") (pin "3") (pinfunction "3_3") (pintype "bidirectional"))
      (node (ref "M1") (pin "J5.3") (pinfunction "RX+_J5.3") (pintype "bidirectional"))
      (node (ref "T3") (pin "11") (pinfunction "11_11") (pintype "bidirectional"))
    )
    (net (code "26") (name "ETH5_RX-") (class "Default")
      (node (ref "CON8") (pin "4") (pinfunction "4_4") (pintype "bidirectional"))
      (node (ref "M1") (pin "J5.6") (pinfunction "RX-_J5.6") (pintype "bidirectional"))
      (node (ref "T3") (pin "9") (pinfunction "9_9") (pintype "bidirectional"))
    )
    (net (code "27") (name "ETH5_TX+") (class "Default")
      (node (ref "CON8") (pin "1") (pinfunction "1_1") (pintype "bidirectional"))
      (node (ref "M1") (pin "J5.1") (pinfunction "TX+_J5.1") (pintype "bidirectional"))
      (node (ref "T3") (pin "16") (pinfunction "16_16") (pintype "bidirectional"))
    )
    (net (code "28") (name "ETH5_TX-") (class "Default")
      (node (ref "CON8") (pin "2") (pinfunction "2_2") (pintype "bidirectional"))
      (node (ref "M1") (pin "J5.2") (pinfunction "TX-_J5.2") (pintype "bidirectional"))
      (node (ref "T3") (pin "14") (pinfunction "14_14") (pintype "bidirectional"))
    )
    (net (code "29") (name "GND") (class "Default")
      (node (ref "C4") (pin "P$1") (pinfunction "1_P$1") (pintype "passive"))
      (node (ref "C8") (pin "P$2") (pinfunction "2_P$2") (pintype "passive"))
      (node (ref "CON1") (pin "13") (pinfunction "GND_13") (pintype "bidirectional"))
      (node (ref "CON1") (pin "15") (pinfunction "GND_15") (pintype "bidirectional"))
      (node (ref "CON1") (pin "55") (pinfunction "~{VDD_BRICK_VALID\\}_55") (pintype "bidirectional"))
      (node (ref "CON11") (pin "1") (pinfunction "1_1") (pintype "bidirectional"))
      (node (ref "CON12") (pin "1") (pinfunction "1_1") (pintype "passive"))
      (node (ref "CON12") (pin "2") (pinfunction "2_2") (pintype "passive"))
      (node (ref "CON12") (pin "3") (pinfunction "3_3") (pintype "passive"))
      (node (ref "CON13") (pin "6") (pinfunction "6_6") (pintype "bidirectional"))
      (node (ref "CON14") (pin "1") (pinfunction "1_1") (pintype "passive"))
      (node (ref "CON15") (pin "1") (pinfunction "1_1") (pintype "bidirectional"))
      (node (ref "CON16") (pin "6") (pinfunction "6_6") (pintype "bidirectional"))
      (node (ref "CON17") (pin "1") (pinfunction "1_1") (pintype "bidirectional"))
      (node (ref "CON18") (pin "1") (pinfunction "1_1") (pintype "bidirectional"))
      (node (ref "CON18") (pin "6") (pinfunction "6_6") (pintype "bidirectional"))
      (node (ref "CON19") (pin "A1") (pinfunction "GND_A1") (pintype "bidirectional"))
      (node (ref "CON19") (pin "A12") (pinfunction "GND_A12") (pintype "bidirectional"))
      (node (ref "CON19") (pin "B1") (pinfunction "GND_B1") (pintype "bidirectional"))
      (node (ref "CON19") (pin "B12") (pinfunction "GND_B12") (pintype "bidirectional"))
      (node (ref "CON19") (pin "G1") (pinfunction "GND_G1") (pintype "bidirectional"))
      (node (ref "CON19") (pin "G10") (pinfunction "GND_G10") (pintype "bidirectional"))
      (node (ref "CON19") (pin "G2") (pinfunction "GND_G2") (pintype "bidirectional"))
      (node (ref "CON19") (pin "G4") (pinfunction "GND_G4") (pintype "bidirectional"))
      (node (ref "CON19") (pin "G5") (pinfunction "GND_G5") (pintype "bidirectional"))
      (node (ref "CON19") (pin "G7") (pinfunction "GND_G7") (pintype "bidirectional"))
      (node (ref "CON19") (pin "G8") (pinfunction "GND_G8") (pintype "bidirectional"))
      (node (ref "CON19") (pin "G9") (pinfunction "GND_G9") (pintype "bidirectional"))
      (node (ref "CON19") (pin "P$1") (pinfunction "GND_P$1") (pintype "bidirectional"))
      (node (ref "CON19") (pin "P$2") (pinfunction "GND_P$2") (pintype "bidirectional"))
      (node (ref "CON2") (pin "1") (pinfunction "1_1") (pintype "bidirectional"))
      (node (ref "CON2") (pin "4") (pinfunction "4_4") (pintype "bidirectional"))
      (node (ref "CON20") (pin "4") (pinfunction "4_4") (pintype "passive"))
      (node (ref "CON20") (pin "5") (pinfunction "5_5") (pintype "passive"))
      (node (ref "CON20") (pin "6") (pinfunction "6_6") (pintype "passive"))
      (node (ref "CON22") (pin "4") (pinfunction "4_4") (pintype "bidirectional"))
      (node (ref "CON23") (pin "4") (pinfunction "4_4") (pintype "bidirectional"))
      (node (ref "CON24") (pin "4") (pinfunction "4_4") (pintype "bidirectional"))
      (node (ref "CON25") (pin "4") (pinfunction "4_4") (pintype "bidirectional"))
      (node (ref "CON26") (pin "4") (pinfunction "4_4") (pintype "bidirectional"))
      (node (ref "CON27") (pin "4") (pinfunction "4_4") (pintype "bidirectional"))
      (node (ref "CON28") (pin "4") (pinfunction "4_4") (pintype "bidirectional"))
      (node (ref "CON29") (pin "1") (pinfunction "1_1") (pintype "bidirectional"))
      (node (ref "CON30") (pin "1") (pinfunction "1_1") (pintype "bidirectional"))
      (node (ref "CON32") (pin "1") (pinfunction "1_1") (pintype "bidirectional"))
      (node (ref "CON5") (pin "5") (pinfunction "5_5") (pintype "bidirectional"))
      (node (ref "CON5") (pin "6") (pinfunction "6_6") (pintype "bidirectional"))
      (node (ref "CON6") (pin "4") (pinfunction "4_4") (pintype "bidirectional"))
      (node (ref "CON7") (pin "1") (pinfunction "1_1") (pintype "passive"))
      (node (ref "CON7") (pin "2") (pinfunction "2_2") (pintype "passive"))
      (node (ref "CON7") (pin "3") (pinfunction "3_3") (pintype "passive"))
      (node (ref "CON8") (pin "6") (pinfunction "6_6") (pintype "bidirectional"))
      (node (ref "CON9") (pin "11") (pinfunction "11_11") (pintype "passive"))
      (node (ref "CON9") (pin "12") (pinfunction "12_12") (pintype "passive"))
      (node (ref "CON9") (pin "3") (pinfunction "3_3") (pintype "passive"))
      (node (ref "CON9") (pin "4") (pinfunction "4_4") (pintype "passive"))
      (node (ref "CON9") (pin "5") (pinfunction "5_5") (pintype "passive"))
      (node (ref "D10") (pin "3") (pinfunction "A_3") (pintype "bidirectional"))
      (node (ref "D11") (pin "A") (pinfunction "A_A") (pintype "passive"))
      (node (ref "D12") (pin "3") (pinfunction "A_3") (pintype "bidirectional"))
      (node (ref "D2") (pin "3") (pinfunction "A_3") (pintype "bidirectional"))
      (node (ref "D3") (pin "3") (pinfunction "A_3") (pintype "bidirectional"))
      (node (ref "IC5") (pin "2") (pinfunction "GND_2") (pintype "bidirectional"))
      (node (ref "LED1") (pin "C") (pinfunction "C_C") (pintype "bidirectional"))
      (node (ref "LED2") (pin "C") (pinfunction "C_C") (pintype "bidirectional"))
      (node (ref "LED3") (pin "C") (pinfunction "C_C") (pintype "bidirectional"))
      (node (ref "LED5") (pin "C") (pinfunction "C_C") (pintype "bidirectional"))
      (node (ref "M1") (pin "GND") (pinfunction "GND_GND") (pintype "bidirectional"))
      (node (ref "MODULE1") (pin "12") (pinfunction "GND_12") (pintype "bidirectional"))
      (node (ref "MODULE1") (pin "16") (pinfunction "GND_16") (pintype "bidirectional"))
      (node (ref "MODULE1") (pin "20") (pinfunction "GND_20") (pintype "bidirectional"))
      (node (ref "MODULE1") (pin "22") (pinfunction "GND_22") (pintype "bidirectional"))
      (node (ref "MODULE1") (pin "24") (pinfunction "GND_24") (pintype "bidirectional"))
      (node (ref "MODULE1") (pin "4") (pinfunction "GND_4") (pintype "bidirectional"))
      (node (ref "MODULE1") (pin "8") (pinfunction "GND_8") (pintype "bidirectional"))
      (node (ref "MODULE2") (pin "1") (pinfunction "GND_1") (pintype "bidirectional"))
      (node (ref "MODULE2") (pin "21") (pinfunction "GND_21") (pintype "bidirectional"))
      (node (ref "MODULE2") (pin "23") (pinfunction "GND_23") (pintype "bidirectional"))
      (node (ref "MODULE2") (pin "4") (pinfunction "GND_4") (pintype "bidirectional"))
      (node (ref "MODULE2") (pin "56") (pinfunction "GND_56") (pintype "bidirectional"))
      (node (ref "MODULE2") (pin "P$1") (pinfunction "GND_P$1") (pintype "bidirectional"))
      (node (ref "MODULE2") (pin "P$2") (pinfunction "GND_P$2") (pintype "bidirectional"))
      (node (ref "MODULE2") (pin "P$3") (pinfunction "GND_P$3") (pintype "bidirectional"))
      (node (ref "Q1") (pin "2") (pinfunction "S_2") (pintype "passive"))
      (node (ref "R16") (pin "1") (pinfunction "1_1") (pintype "passive"))
      (node (ref "R31") (pin "2") (pinfunction "2_2") (pintype "passive"))
    )
    (net (code "30") (name "HLK_RX0") (class "Default")
      (node (ref "CON16") (pin "2") (pinfunction "2_2") (pintype "bidirectional"))
      (node (ref "MODULE2") (pin "32") (pinfunction "UART_RXD0_32") (pintype "bidirectional"))
      (node (ref "R14") (pin "1") (pinfunction "1_1") (pintype "passive"))
    )
    (net (code "31") (name "HLK_RX1") (class "Default")
      (node (ref "MODULE2") (pin "16") (pinfunction "UART_RXD1_16") (pintype "bidirectional"))
      (node (ref "R6") (pin "1") (pinfunction "1_1") (pintype "passive"))
    )
    (net (code "32") (name "HLK_TX0") (class "Default")
      (node (ref "CON16") (pin "1") (pinfunction "1_1") (pintype "bidirectional"))
      (node (ref "MODULE2") (pin "31") (pinfunction "UART_TXD0_31") (pintype "bidirectional"))
      (node (ref "R15") (pin "1") (pinfunction "1_1") (pintype "passive"))
    )
    (net (code "33") (name "HLK_TX1") (class "Default")
      (node (ref "MODULE2") (pin "15") (pinfunction "UART_TXD1_15") (pintype "bidirectional"))
      (node (ref "R7") (pin "1") (pinfunction "1_1") (pintype "passive"))
    )
    (net (code "34") (name "I2C2_SCL") (class "Default")
      (node (ref "CON1") (pin "6") (pinfunction "I2C2_SCL_6") (pintype "bidirectional"))
      (node (ref "D12") (pin "2") (pinfunction "C1_2") (pintype "bidirectional"))
      (node (ref "R35") (pin "2") (pinfunction "2_2") (pintype "passive"))
    )
    (net (code "35") (name "I2C2_SDA") (class "Default")
      (node (ref "CON1") (pin "4") (pinfunction "I2C2_SDA_4") (pintype "bidirectional"))
      (node (ref "D12") (pin "1") (pinfunction "C_1") (pintype "bidirectional"))
      (node (ref "R36") (pin "2") (pinfunction "2_2") (pintype "passive"))
    )
    (net (code "36") (name "M1PWM") (class "Default")
      (node (ref "CON1") (pin "50") (pinfunction "FMU-CH1-PROT_50") (pintype "bidirectional"))
      (node (ref "CON27") (pin "1") (pinfunction "1_1") (pintype "bidirectional"))
    )
    (net (code "37") (name "M2PWM") (class "Default")
      (node (ref "CON1") (pin "52") (pinfunction "FMU-CH2-PROT_52") (pintype "bidirectional"))
      (node (ref "CON26") (pin "1") (pinfunction "1_1") (pintype "bidirectional"))
    )
    (net (code "38") (name "M3PWM") (class "Default")
      (node (ref "CON1") (pin "54") (pinfunction "FMU-CH3-PROT_54") (pintype "bidirectional"))
      (node (ref "CON25") (pin "1") (pinfunction "1_1") (pintype "bidirectional"))
    )
    (net (code "39") (name "M4PWM") (class "Default")
      (node (ref "CON1") (pin "56") (pinfunction "FMU-CH4-PROT_56") (pintype "bidirectional"))
      (node (ref "CON24") (pin "1") (pinfunction "1_1") (pintype "bidirectional"))
    )
    (net (code "40") (name "M5PWM") (class "Default")
      (node (ref "CON1") (pin "58") (pinfunction "FMU-CH5-PROT_58") (pintype "bidirectional"))
      (node (ref "CON23") (pin "1") (pinfunction "1_1") (pintype "bidirectional"))
    )
    (net (code "41") (name "M6PWM") (class "Default")
      (node (ref "CON1") (pin "60") (pinfunction "FMU-CH6-PROT_60") (pintype "bidirectional"))
      (node (ref "CON22") (pin "1") (pinfunction "1_1") (pintype "bidirectional"))
    )
    (net (code "42") (name "Net-(BUZ1-+)") (class "Default")
      (node (ref "BUZ1") (pin "1") (pinfunction "+_1") (pintype "bidirectional"))
      (node (ref "R22") (pin "P$1") (pinfunction "1_P$1") (pintype "passive"))
      (node (ref "R23") (pin "P$1") (pinfunction "1_P$1") (pintype "passive"))
    )
    (net (code "43") (name "Net-(BUZ1--)") (class "Default")
      (node (ref "BUZ1") (pin "2") (pinfunction "-_2") (pintype "bidirectional"))
      (node (ref "Q1") (pin "3") (pinfunction "D_3") (pintype "passive"))
    )
    (net (code "44") (name "Net-(CON1-~{FMU_LED_AMBER})") (class "Default")
      (node (ref "CON1") (pin "2") (pinfunction "~{FMU_LED_AMBER}_2") (pintype "bidirectional"))
      (node (ref "LED4") (pin "C") (pinfunction "C_C") (pintype "bidirectional"))
    )
    (net (code "45") (name "Net-(CON10-Pad1)") (class "Default")
      (node (ref "CON10") (pin "1") (pinfunction "1_1") (pintype "passive"))
      (node (ref "CON4") (pin "1") (pinfunction "1_1") (pintype "bidirectional"))
    )
    (net (code "46") (name "Net-(CON10-Pad2)") (class "Default")
      (node (ref "CON10") (pin "2") (pinfunction "2_2") (pintype "passive"))
      (node (ref "CON4") (pin "2") (pinfunction "2_2") (pintype "bidirectional"))
    )
    (net (code "47") (name "Net-(CON15-Pad3)") (class "Default")
      (node (ref "CON15") (pin "3") (pinfunction "3_3") (pintype "bidirectional"))
      (node (ref "R35") (pin "1") (pinfunction "1_1") (pintype "passive"))
    )
    (net (code "48") (name "Net-(CON15-Pad4)") (class "Default")
      (node (ref "CON15") (pin "4") (pinfunction "4_4") (pintype "bidirectional"))
      (node (ref "R36") (pin "1") (pinfunction "1_1") (pintype "passive"))
    )
    (net (code "49") (name "Net-(CON17-Pad3)") (class "Default")
      (node (ref "CON17") (pin "3") (pinfunction "3_3") (pintype "bidirectional"))
      (node (ref "R37") (pin "1") (pinfunction "1_1") (pintype "passive"))
    )
    (net (code "50") (name "Net-(CON17-Pad4)") (class "Default")
      (node (ref "CON17") (pin "4") (pinfunction "4_4") (pintype "bidirectional"))
      (node (ref "R38") (pin "1") (pinfunction "1_1") (pintype "passive"))
    )
    (net (code "51") (name "Net-(CON18-Pad3)") (class "Default")
      (node (ref "CON18") (pin "3") (pinfunction "3_3") (pintype "bidirectional"))
      (node (ref "R4") (pin "1") (pinfunction "1_1") (pintype "passive"))
    )
    (net (code "52") (name "Net-(CON18-Pad4)") (class "Default")
      (node (ref "CON18") (pin "4") (pinfunction "4_4") (pintype "bidirectional"))
      (node (ref "R5") (pin "1") (pinfunction "1_1") (pintype "passive"))
    )
    (net (code "53") (name "Net-(CON18-Pad5)") (class "Default")
      (node (ref "CON18") (pin "5") (pinfunction "5_5") (pintype "bidirectional"))
      (node (ref "R12") (pin "1") (pinfunction "1_1") (pintype "passive"))
    )
    (net (code "54") (name "Net-(IC5-BST)") (class "Default")
      (node (ref "C56") (pin "2") (pinfunction "2_2") (pintype "passive"))
      (node (ref "IC5") (pin "1") (pinfunction "BST_1") (pintype "bidirectional"))
    )
    (net (code "55") (name "Net-(IC5-EN)") (class "Default")
      (node (ref "IC5") (pin "4") (pinfunction "EN_4") (pintype "bidirectional"))
      (node (ref "R32") (pin "1") (pinfunction "1_1") (pintype "passive"))
    )
    (net (code "56") (name "Net-(IC5-FB)") (class "Default")
      (node (ref "IC5") (pin "3") (pinfunction "FB_3") (pintype "bidirectional"))
      (node (ref "R30") (pin "1") (pinfunction "1_1") (pintype "passive"))
      (node (ref "R31") (pin "1") (pinfunction "1_1") (pintype "passive"))
    )
    (net (code "57") (name "Net-(IC5-SW)") (class "Default")
      (node (ref "C56") (pin "1") (pinfunction "1_1") (pintype "passive"))
      (node (ref "D11") (pin "C") (pinfunction "C_C") (pintype "passive"))
      (node (ref "IC5") (pin "6") (pinfunction "SW_6") (pintype "bidirectional"))
      (node (ref "L1") (pin "P$1") (pinfunction "1_P$1") (pintype "bidirectional"))
    )
    (net (code "58") (name "Net-(LED1-PadA)") (class "Default")
      (node (ref "LED1") (pin "A") (pinfunction "A_A") (pintype "bidirectional"))
      (node (ref "R8") (pin "1") (pinfunction "1_1") (pintype "passive"))
    )
    (net (code "59") (name "Net-(LED2-PadA)") (class "Default")
      (node (ref "LED2") (pin "A") (pinfunction "A_A") (pintype "bidirectional"))
      (node (ref "R9") (pin "1") (pinfunction "1_1") (pintype "passive"))
    )
    (net (code "60") (name "Net-(LED3-PadA)") (class "Default")
      (node (ref "LED3") (pin "A") (pinfunction "A_A") (pintype "bidirectional"))
      (node (ref "R10") (pin "1") (pinfunction "1_1") (pintype "passive"))
    )
    (net (code "61") (name "Net-(LED4-PadA)") (class "Default")
      (node (ref "LED4") (pin "A") (pinfunction "A_A") (pintype "bidirectional"))
      (node (ref "R18") (pin "2") (pinfunction "2_2") (pintype "passive"))
    )
    (net (code "62") (name "Net-(LED5-PadA)") (class "Default")
      (node (ref "LED5") (pin "A") (pinfunction "A_A") (pintype "bidirectional"))
      (node (ref "R11") (pin "1") (pinfunction "1_1") (pintype "passive"))
    )
    (net (code "63") (name "Net-(MODULE1-RX_1)") (class "Default")
      (node (ref "MODULE1") (pin "17") (pinfunction "RX_1_17") (pintype "bidirectional"))
      (node (ref "R3") (pin "1") (pinfunction "1_1") (pintype "passive"))
    )
    (net (code "64") (name "Net-(MODULE1-TX_1)") (class "Default")
      (node (ref "MODULE1") (pin "19") (pinfunction "TX_1_19") (pintype "bidirectional"))
      (node (ref "R1") (pin "1") (pinfunction "1_1") (pintype "passive"))
    )
    (net (code "65") (name "Net-(MODULE2-EPHY_LED0)") (class "Default")
      (node (ref "MODULE2") (pin "13") (pinfunction "EPHY_LED0_13") (pintype "bidirectional"))
      (node (ref "R11") (pin "2") (pinfunction "2_2") (pintype "passive"))
    )
    (net (code "66") (name "Net-(MODULE2-EPHY_LED1)") (class "Default")
      (node (ref "MODULE2") (pin "12") (pinfunction "EPHY_LED1_12") (pintype "bidirectional"))
      (node (ref "R10") (pin "2") (pinfunction "2_2") (pintype "passive"))
    )
    (net (code "67") (name "Net-(MODULE2-EPHY_LED2)") (class "Default")
      (node (ref "MODULE2") (pin "11") (pinfunction "EPHY_LED2_11") (pintype "bidirectional"))
      (node (ref "R9") (pin "2") (pinfunction "2_2") (pintype "passive"))
    )
    (net (code "68") (name "Net-(MODULE2-EPHY_LED4)") (class "Default")
      (node (ref "MODULE2") (pin "9") (pinfunction "EPHY_LED4_9") (pintype "bidirectional"))
      (node (ref "R8") (pin "2") (pinfunction "2_2") (pintype "passive"))
    )
    (net (code "69") (name "Net-(MODULE2-USB_DM)") (class "Default")
      (node (ref "MODULE2") (pin "55") (pinfunction "USB_DM_55") (pintype "bidirectional"))
      (node (ref "PAD2") (pin "1") (pinfunction "P$1_1") (pintype "bidirectional"))
    )
    (net (code "70") (name "Net-(MODULE2-USB_DP)") (class "Default")
      (node (ref "MODULE2") (pin "54") (pinfunction "USB_DP_54") (pintype "bidirectional"))
      (node (ref "PAD1") (pin "1") (pinfunction "P$1_1") (pintype "bidirectional"))
    )
    (net (code "71") (name "Net-(Q1-G)") (class "Default")
      (node (ref "Q1") (pin "1") (pinfunction "G_1") (pintype "passive"))
      (node (ref "R16") (pin "2") (pinfunction "2_2") (pintype "passive"))
      (node (ref "R20") (pin "1") (pinfunction "1_1") (pintype "passive"))
    )
    (net (code "72") (name "Net-(R2-Pad2)") (class "Default")
      (node (ref "R2") (pin "2") (pinfunction "2_2") (pintype "passive"))
      (node (ref "SJ2") (pin "1") (pinfunction "1_1") (pintype "passive"))
    )
    (net (code "73") (name "OTG_DM1") (class "Default")
      (node (ref "CON1") (pin "33") (pinfunction "OTG_DM1_33") (pintype "bidirectional"))
      (node (ref "CON14") (pin "4") (pinfunction "4_4") (pintype "passive"))
      (node (ref "CON19") (pin "A7") (pinfunction "D-_A7") (pintype "bidirectional"))
      (node (ref "CON19") (pin "B7") (pinfunction "D-_B7") (pintype "bidirectional"))
    )
    (net (code "74") (name "OTG_DP1") (class "Default")
      (node (ref "CON1") (pin "31") (pinfunction "OTG_DP1_31") (pintype "bidirectional"))
      (node (ref "CON14") (pin "3") (pinfunction "3_3") (pintype "passive"))
      (node (ref "CON19") (pin "A6") (pinfunction "D+_A6") (pintype "bidirectional"))
      (node (ref "CON19") (pin "B6") (pinfunction "D+_B6") (pintype "bidirectional"))
    )
    (net (code "75") (name "P0_RX+") (class "Default")
      (node (ref "MODULE2") (pin "34") (pinfunction "MDI_RP_P0_34") (pintype "bidirectional"))
      (node (ref "T2") (pin "6") (pinfunction "6_6") (pintype "bidirectional"))
    )
    (net (code "76") (name "P0_RX-") (class "Default")
      (node (ref "MODULE2") (pin "35") (pinfunction "MDI_RN_P0_35") (pintype "bidirectional"))
      (node (ref "T2") (pin "8") (pinfunction "8_8") (pintype "bidirectional"))
    )
    (net (code "77") (name "P0_TX+") (class "Default")
      (node (ref "MODULE2") (pin "36") (pinfunction "MDI_TP_P0_36") (pintype "bidirectional"))
      (node (ref "T2") (pin "1") (pinfunction "1_1") (pintype "bidirectional"))
    )
    (net (code "78") (name "P0_TX-") (class "Default")
      (node (ref "MODULE2") (pin "37") (pinfunction "MDI_TN_P0_37") (pintype "bidirectional"))
      (node (ref "T2") (pin "3") (pinfunction "3_3") (pintype "bidirectional"))
    )
    (net (code "79") (name "P1_RX+") (class "Default")
      (node (ref "MODULE2") (pin "40") (pinfunction "MDI_RP_P1_40") (pintype "bidirectional"))
      (node (ref "T1") (pin "6") (pinfunction "6_6") (pintype "bidirectional"))
    )
    (net (code "80") (name "P1_RX-") (class "Default")
      (node (ref "MODULE2") (pin "41") (pinfunction "MDI_RN_P1_41") (pintype "bidirectional"))
      (node (ref "T1") (pin "8") (pinfunction "8_8") (pintype "bidirectional"))
    )
    (net (code "81") (name "P1_TX+") (class "Default")
      (node (ref "MODULE2") (pin "38") (pinfunction "MDI_TP_P1_38") (pintype "bidirectional"))
      (node (ref "T1") (pin "1") (pinfunction "1_1") (pintype "bidirectional"))
    )
    (net (code "82") (name "P1_TX-") (class "Default")
      (node (ref "MODULE2") (pin "39") (pinfunction "MDI_TN_P1_39") (pintype "bidirectional"))
      (node (ref "T1") (pin "3") (pinfunction "3_3") (pintype "bidirectional"))
    )
    (net (code "83") (name "P2_RX+") (class "Default")
      (node (ref "MODULE2") (pin "42") (pinfunction "MDI_RP_P2_42") (pintype "bidirectional"))
      (node (ref "T4") (pin "6") (pinfunction "6_6") (pintype "bidirectional"))
    )
    (net (code "84") (name "P2_RX-") (class "Default")
      (node (ref "MODULE2") (pin "43") (pinfunction "MDI_RN_P2_43") (pintype "bidirectional"))
      (node (ref "T4") (pin "8") (pinfunction "8_8") (pintype "bidirectional"))
    )
    (net (code "85") (name "P2_TX+") (class "Default")
      (node (ref "MODULE2") (pin "44") (pinfunction "MDI_TP_P2_44") (pintype "bidirectional"))
      (node (ref "T4") (pin "1") (pinfunction "1_1") (pintype "bidirectional"))
    )
    (net (code "86") (name "P2_TX-") (class "Default")
      (node (ref "MODULE2") (pin "45") (pinfunction "MDI_TN_P2_45") (pintype "bidirectional"))
      (node (ref "T4") (pin "3") (pinfunction "3_3") (pintype "bidirectional"))
    )
    (net (code "87") (name "P4_RX+") (class "Default")
      (node (ref "MODULE2") (pin "50") (pinfunction "MDI_RP_P4_50") (pintype "bidirectional"))
      (node (ref "T3") (pin "6") (pinfunction "6_6") (pintype "bidirectional"))
    )
    (net (code "88") (name "P4_RX-") (class "Default")
      (node (ref "MODULE2") (pin "51") (pinfunction "MDI_RN_P4_51") (pintype "bidirectional"))
      (node (ref "T3") (pin "8") (pinfunction "8_8") (pintype "bidirectional"))
    )
    (net (code "89") (name "P4_TX+") (class "Default")
      (node (ref "MODULE2") (pin "52") (pinfunction "MDI_TP_P4_52") (pintype "bidirectional"))
      (node (ref "T3") (pin "1") (pinfunction "1_1") (pintype "bidirectional"))
    )
    (net (code "90") (name "P4_TX-") (class "Default")
      (node (ref "MODULE2") (pin "53") (pinfunction "MDI_TN_P4_53") (pintype "bidirectional"))
      (node (ref "T3") (pin "3") (pinfunction "3_3") (pintype "bidirectional"))
    )
    (net (code "91") (name "PPM-SBUS-PROT") (class "Default")
      (node (ref "CON1") (pin "62") (pinfunction "PPM-SBUS-PROT_62") (pintype "bidirectional"))
      (node (ref "D3") (pin "1") (pinfunction "C_1") (pintype "bidirectional"))
      (node (ref "R12") (pin "2") (pinfunction "2_2") (pintype "passive"))
    )
    (net (code "92") (name "RX_2") (class "Default")
      (node (ref "CON29") (pin "3") (pinfunction "3_3") (pintype "bidirectional"))
      (node (ref "MODULE1") (pin "13") (pinfunction "RX_2_13") (pintype "bidirectional"))
      (node (ref "R14") (pin "2") (pinfunction "2_2") (pintype "passive"))
    )
    (net (code "93") (name "RX_3") (class "Default")
      (node (ref "CON32") (pin "3") (pinfunction "3_3") (pintype "bidirectional"))
      (node (ref "MODULE1") (pin "9") (pinfunction "RX_3_9") (pintype "bidirectional"))
    )
    (net (code "94") (name "RX_4") (class "Default")
      (node (ref "CON5") (pin "3") (pinfunction "3_3") (pintype "bidirectional"))
      (node (ref "MODULE1") (pin "5") (pinfunction "RX_4_5") (pintype "bidirectional"))
    )
    (net (code "95") (name "SERIAL1_RX") (class "Default")
      (node (ref "CON1") (pin "38") (pinfunction "SERIAL1_RX_38") (pintype "bidirectional"))
      (node (ref "D2") (pin "1") (pinfunction "C_1") (pintype "bidirectional"))
      (node (ref "R1") (pin "2") (pinfunction "2_2") (pintype "passive"))
      (node (ref "R5") (pin "2") (pinfunction "2_2") (pintype "passive"))
      (node (ref "R7") (pin "2") (pinfunction "2_2") (pintype "passive"))
    )
    (net (code "96") (name "SERIAL1_TX") (class "Default")
      (node (ref "CON1") (pin "40") (pinfunction "SERIAL1_TX_40") (pintype "bidirectional"))
      (node (ref "D2") (pin "2") (pinfunction "C1_2") (pintype "bidirectional"))
      (node (ref "R3") (pin "2") (pinfunction "2_2") (pintype "passive"))
      (node (ref "R4") (pin "2") (pinfunction "2_2") (pintype "passive"))
      (node (ref "R6") (pin "2") (pinfunction "2_2") (pintype "passive"))
    )
    (net (code "97") (name "SERIAL2_RX") (class "Default")
      (node (ref "CON1") (pin "34") (pinfunction "SERIAL2_RX_34") (pintype "bidirectional"))
      (node (ref "D10") (pin "2") (pinfunction "C1_2") (pintype "bidirectional"))
      (node (ref "R38") (pin "2") (pinfunction "2_2") (pintype "passive"))
    )
    (net (code "98") (name "SERIAL2_TX") (class "Default")
      (node (ref "CON1") (pin "36") (pinfunction "SERIAL2_TX_36") (pintype "bidirectional"))
      (node (ref "D10") (pin "1") (pinfunction "C_1") (pintype "bidirectional"))
      (node (ref "R37") (pin "2") (pinfunction "2_2") (pintype "passive"))
    )
    (net (code "99") (name "SERIAL3_RX") (class "Default")
      (node (ref "CON1") (pin "20") (pinfunction "SERIAL3_RX_20") (pintype "bidirectional"))
      (node (ref "CON16") (pin "4") (pinfunction "4_4") (pintype "bidirectional"))
    )
    (net (code "100") (name "SERIAL3_TX") (class "Default")
      (node (ref "CON1") (pin "22") (pinfunction "SERIAL3_TX_22") (pintype "bidirectional"))
      (node (ref "CON16") (pin "3") (pinfunction "3_3") (pintype "bidirectional"))
    )
    (net (code "101") (name "SERIAL4_RX") (class "Default")
      (node (ref "CON1") (pin "16") (pinfunction "SERIAL4_RX_16") (pintype "bidirectional"))
      (node (ref "CON11") (pin "4") (pinfunction "4_4") (pintype "bidirectional"))
    )
    (net (code "102") (name "SERIAL4_TX") (class "Default")
      (node (ref "CON1") (pin "18") (pinfunction "SERIAL4_TX_18") (pintype "bidirectional"))
      (node (ref "CON11") (pin "3") (pinfunction "3_3") (pintype "bidirectional"))
    )
    (net (code "103") (name "SERIAL5_RX") (class "Default")
      (node (ref "CON1") (pin "12") (pinfunction "SERIAL5_RX_12") (pintype "bidirectional"))
      (node (ref "CON30") (pin "4") (pinfunction "4_4") (pintype "bidirectional"))
    )
    (net (code "104") (name "SERIAL5_TX") (class "Default")
      (node (ref "CON1") (pin "14") (pinfunction "SERIAL5_TX_14") (pintype "bidirectional"))
      (node (ref "CON30") (pin "3") (pinfunction "3_3") (pintype "bidirectional"))
    )
    (net (code "105") (name "TX_2") (class "Default")
      (node (ref "CON29") (pin "4") (pinfunction "4_4") (pintype "bidirectional"))
      (node (ref "MODULE1") (pin "15") (pinfunction "TX_2_15") (pintype "bidirectional"))
      (node (ref "R15") (pin "2") (pinfunction "2_2") (pintype "passive"))
    )
    (net (code "106") (name "TX_3") (class "Default")
      (node (ref "CON32") (pin "4") (pinfunction "4_4") (pintype "bidirectional"))
      (node (ref "MODULE1") (pin "11") (pinfunction "TX_3_11") (pintype "bidirectional"))
    )
    (net (code "107") (name "TX_4") (class "Default")
      (node (ref "CON5") (pin "4") (pinfunction "4_4") (pintype "bidirectional"))
      (node (ref "MODULE1") (pin "7") (pinfunction "TX_4_7") (pintype "bidirectional"))
    )
    (net (code "108") (name "VBUS") (class "Default")
      (node (ref "CON1") (pin "29") (pinfunction "VBUS_29") (pintype "bidirectional"))
      (node (ref "CON14") (pin "2") (pinfunction "2_2") (pintype "passive"))
      (node (ref "CON19") (pin "A4") (pinfunction "VBUS_A4") (pintype "bidirectional"))
      (node (ref "CON19") (pin "B4") (pinfunction "VBUS_B4") (pintype "bidirectional"))
      (node (ref "D1") (pin "A") (pinfunction "A_A") (pintype "passive"))
    )
    (net (code "109") (name "VDD_3V3") (class "Default")
      (node (ref "C8") (pin "P$1") (pinfunction "1_P$1") (pintype "passive"))
      (node (ref "L1") (pin "P$2") (pinfunction "2_P$2") (pintype "bidirectional"))
      (node (ref "MODULE2") (pin "2") (pinfunction "3.3V_2") (pintype "bidirectional"))
      (node (ref "MODULE2") (pin "3") (pinfunction "3.3V_3") (pintype "bidirectional"))
      (node (ref "R30") (pin "2") (pinfunction "2_2") (pintype "passive"))
    )
    (net (code "110") (name "VDD_4V") (class "Default")
      (node (ref "CON9") (pin "10") (pinfunction "10_10") (pintype "passive"))
      (node (ref "CON9") (pin "9") (pinfunction "9_9") (pintype "passive"))
      (node (ref "MODULE1") (pin "21") (pinfunction "VCC_21") (pintype "bidirectional"))
      (node (ref "MODULE1") (pin "23") (pinfunction "VCC_23") (pintype "bidirectional"))
    )
    (net (code "111") (name "VDD_5V") (class "Default")
      (node (ref "CON11") (pin "2") (pinfunction "2_2") (pintype "bidirectional"))
      (node (ref "CON17") (pin "2") (pinfunction "2_2") (pintype "bidirectional"))
      (node (ref "CON18") (pin "2") (pinfunction "2_2") (pintype "bidirectional"))
      (node (ref "CON28") (pin "1") (pinfunction "1_1") (pintype "bidirectional"))
      (node (ref "CON30") (pin "2") (pinfunction "2_2") (pintype "bidirectional"))
      (node (ref "CON6") (pin "1") (pinfunction "1_1") (pintype "bidirectional"))
      (node (ref "CON7") (pin "4") (pinfunction "4_4") (pintype "passive"))
      (node (ref "CON7") (pin "5") (pinfunction "5_5") (pintype "passive"))
      (node (ref "CON7") (pin "6") (pinfunction "6_6") (pintype "passive"))
      (node (ref "R23") (pin "P$2") (pinfunction "2_P$2") (pintype "passive"))
    )
    (net (code "112") (name "VDD_12V") (class "Default")
      (node (ref "C4") (pin "P$2") (pinfunction "2_P$2") (pintype "passive"))
      (node (ref "CON13") (pin "1") (pinfunction "1_1") (pintype "bidirectional"))
      (node (ref "CON15") (pin "2") (pinfunction "2_2") (pintype "bidirectional"))
      (node (ref "CON2") (pin "2") (pinfunction "2_2") (pintype "bidirectional"))
      (node (ref "CON2") (pin "3") (pinfunction "3_3") (pintype "bidirectional"))
      (node (ref "CON20") (pin "1") (pinfunction "1_1") (pintype "passive"))
      (node (ref "CON20") (pin "2") (pinfunction "2_2") (pintype "passive"))
      (node (ref "CON20") (pin "3") (pinfunction "3_3") (pintype "passive"))
      (node (ref "CON5") (pin "1") (pinfunction "1_1") (pintype "bidirectional"))
      (node (ref "IC5") (pin "5") (pinfunction "VIN_5") (pintype "bidirectional"))
      (node (ref "M1") (pin "SUP") (pinfunction "SUP_SUP") (pintype "bidirectional"))
      (node (ref "R22") (pin "P$2") (pinfunction "2_P$2") (pintype "passive"))
      (node (ref "R32") (pin "2") (pinfunction "2_2") (pintype "passive"))
    )
    (net (code "113") (name "VDD_24V") (class "Default")
      (node (ref "CON12") (pin "4") (pinfunction "4_4") (pintype "passive"))
      (node (ref "CON12") (pin "5") (pinfunction "5_5") (pintype "passive"))
      (node (ref "CON12") (pin "6") (pinfunction "6_6") (pintype "passive"))
      (node (ref "CON16") (pin "5") (pinfunction "5_5") (pintype "bidirectional"))
      (node (ref "CON8") (pin "5") (pinfunction "5_5") (pintype "bidirectional"))
    )
    (net (code "114") (name "unconnected-(CON1-3.3V_SPEKTRUM_EN-Pad19)") (class "Default")
      (node (ref "CON1") (pin "19") (pinfunction "3.3V_SPEKTRUM_EN_19") (pintype "bidirectional"))
    )
    (net (code "115") (name "unconnected-(CON1-AUX_BATT_CURRENT_SENS-Pad25)") (class "Default")
      (node (ref "CON1") (pin "25") (pinfunction "AUX_BATT_CURRENT_SENS_25") (pintype "bidirectional"))
    )
    (net (code "116") (name "unconnected-(CON1-AUX_BATT_VOLTAGE_SENS-Pad23)") (class "Default")
      (node (ref "CON1") (pin "23") (pinfunction "AUX_BATT_VOLTAGE_SENS_23") (pintype "bidirectional"))
    )
    (net (code "117") (name "unconnected-(CON1-CAN3_H-Pad10)") (class "Default")
      (node (ref "CON1") (pin "10") (pinfunction "CAN3_H_10") (pintype "bidirectional"))
    )
    (net (code "118") (name "unconnected-(CON1-CAN3_L-Pad8)") (class "Default")
      (node (ref "CON1") (pin "8") (pinfunction "CAN3_L_8") (pintype "bidirectional"))
    )
    (net (code "119") (name "unconnected-(CON1-EXTERN_DRDY-Pad11)") (class "Default")
      (node (ref "CON1") (pin "11") (pinfunction "EXTERN_DRDY_11") (pintype "bidirectional"))
    )
    (net (code "120") (name "unconnected-(CON1-FMU-SWCLK-Pad3)") (class "Default")
      (node (ref "CON1") (pin "3") (pinfunction "FMU-SWCLK_3") (pintype "bidirectional"))
    )
    (net (code "121") (name "unconnected-(CON1-FMU-SWDIO-Pad1)") (class "Default")
      (node (ref "CON1") (pin "1") (pinfunction "FMU-SWDIO_1") (pintype "bidirectional"))
    )
    (net (code "122") (name "unconnected-(CON1-FMU-~{RESET}-Pad7)") (class "Default")
      (node (ref "CON1") (pin "7") (pinfunction "FMU-~{RESET}_7") (pintype "bidirectional"))
    )
    (net (code "123") (name "unconnected-(CON1-I2C1_SCL-Pad37)") (class "Default")
      (node (ref "CON1") (pin "37") (pinfunction "I2C1_SCL_37") (pintype "bidirectional"))
    )
    (net (code "124") (name "unconnected-(CON1-I2C1_SDA-Pad35)") (class "Default")
      (node (ref "CON1") (pin "35") (pinfunction "I2C1_SDA_35") (pintype "bidirectional"))
    )
    (net (code "125") (name "unconnected-(CON1-IO-CH1-PROT-Pad80)") (class "Default")
      (node (ref "CON1") (pin "80") (pinfunction "IO-CH1-PROT_80") (pintype "bidirectional"))
    )
    (net (code "126") (name "unconnected-(CON1-IO-CH2-PROT-Pad78)") (class "Default")
      (node (ref "CON1") (pin "78") (pinfunction "IO-CH2-PROT_78") (pintype "bidirectional"))
    )
    (net (code "127") (name "unconnected-(CON1-IO-CH3-PROT-Pad76)") (class "Default")
      (node (ref "CON1") (pin "76") (pinfunction "IO-CH3-PROT_76") (pintype "bidirectional"))
    )
    (net (code "128") (name "unconnected-(CON1-IO-CH4-PROT-Pad74)") (class "Default")
      (node (ref "CON1") (pin "74") (pinfunction "IO-CH4-PROT_74") (pintype "bidirectional"))
    )
    (net (code "129") (name "unconnected-(CON1-IO-CH5-PROT-Pad72)") (class "Default")
      (node (ref "CON1") (pin "72") (pinfunction "IO-CH5-PROT_72") (pintype "bidirectional"))
    )
    (net (code "130") (name "unconnected-(CON1-IO-CH6-PROT-Pad70)") (class "Default")
      (node (ref "CON1") (pin "70") (pinfunction "IO-CH6-PROT_70") (pintype "bidirectional"))
    )
    (net (code "131") (name "unconnected-(CON1-IO-CH7-PROT-Pad68)") (class "Default")
      (node (ref "CON1") (pin "68") (pinfunction "IO-CH7-PROT_68") (pintype "bidirectional"))
    )
    (net (code "132") (name "unconnected-(CON1-IO-CH8-PROT-Pad66)") (class "Default")
      (node (ref "CON1") (pin "66") (pinfunction "IO-CH8-PROT_66") (pintype "bidirectional"))
    )
    (net (code "133") (name "unconnected-(CON1-IO-SWCLK-Pad71)") (class "Default")
      (node (ref "CON1") (pin "71") (pinfunction "IO-SWCLK_71") (pintype "bidirectional"))
    )
    (net (code "134") (name "unconnected-(CON1-IO-SWDIO-Pad69)") (class "Default")
      (node (ref "CON1") (pin "69") (pinfunction "IO-SWDIO_69") (pintype "bidirectional"))
    )
    (net (code "135") (name "unconnected-(CON1-IO-~{RESET}-Pad75)") (class "Default")
      (node (ref "CON1") (pin "75") (pinfunction "IO-~{RESET}_75") (pintype "bidirectional"))
    )
    (net (code "136") (name "unconnected-(CON1-IO_USART1_RX-Pad48)") (class "Default")
      (node (ref "CON1") (pin "48") (pinfunction "IO_USART1_RX_48") (pintype "bidirectional"))
    )
    (net (code "137") (name "unconnected-(CON1-IO_USART1_TX-Pad46)") (class "Default")
      (node (ref "CON1") (pin "46") (pinfunction "IO_USART1_TX_46") (pintype "bidirectional"))
    )
    (net (code "138") (name "unconnected-(CON1-IO_VDD_3V3-Pad26)") (class "Default")
      (node (ref "CON1") (pin "26") (pinfunction "IO_VDD_3V3_26") (pintype "bidirectional"))
    )
    (net (code "139") (name "unconnected-(CON1-IO_VDD_5V5-Pad65)") (class "Default")
      (node (ref "CON1") (pin "65") (pinfunction "IO_VDD_5V5_65") (pintype "bidirectional"))
    )
    (net (code "140") (name "unconnected-(CON1-PRESSURE_SENS_IN-Pad21)") (class "Default")
      (node (ref "CON1") (pin "21") (pinfunction "PRESSURE_SENS_IN_21") (pintype "bidirectional"))
    )
    (net (code "141") (name "unconnected-(CON1-S.BUS_OUT-Pad64)") (class "Default")
      (node (ref "CON1") (pin "64") (pinfunction "S.BUS_OUT_64") (pintype "bidirectional"))
    )
    (net (code "142") (name "unconnected-(CON1-SAFETY-Pad17)") (class "Default")
      (node (ref "CON1") (pin "17") (pinfunction "SAFETY_17") (pintype "bidirectional"))
    )
    (net (code "143") (name "unconnected-(CON1-SERIAL1_CTS-Pad44)") (class "Default")
      (node (ref "CON1") (pin "44") (pinfunction "SERIAL1_CTS_44") (pintype "bidirectional"))
    )
    (net (code "144") (name "unconnected-(CON1-SERIAL1_RTS-Pad42)") (class "Default")
      (node (ref "CON1") (pin "42") (pinfunction "SERIAL1_RTS_42") (pintype "bidirectional"))
    )
    (net (code "145") (name "unconnected-(CON1-SERIAL2_CTS-Pad32)") (class "Default")
      (node (ref "CON1") (pin "32") (pinfunction "SERIAL2_CTS_32") (pintype "bidirectional"))
    )
    (net (code "146") (name "unconnected-(CON1-SERIAL2_RTS-Pad30)") (class "Default")
      (node (ref "CON1") (pin "30") (pinfunction "SERIAL2_RTS_30") (pintype "bidirectional"))
    )
    (net (code "147") (name "unconnected-(CON1-SPI_EXT_MISO-Pad67)") (class "Default")
      (node (ref "CON1") (pin "67") (pinfunction "SPI_EXT_MISO_67") (pintype "bidirectional"))
    )
    (net (code "148") (name "unconnected-(CON1-SPI_EXT_MOSI-Pad51)") (class "Default")
      (node (ref "CON1") (pin "51") (pinfunction "SPI_EXT_MOSI_51") (pintype "bidirectional"))
    )
    (net (code "149") (name "unconnected-(CON1-SPI_EXT_SCK-Pad73)") (class "Default")
      (node (ref "CON1") (pin "73") (pinfunction "SPI_EXT_SCK_73") (pintype "bidirectional"))
    )
    (net (code "150") (name "unconnected-(CON1-VDD_SERVO-Pad53)") (class "Default")
      (node (ref "CON1") (pin "53") (pinfunction "VDD_SERVO_53") (pintype "bidirectional"))
    )
    (net (code "151") (name "unconnected-(CON1-VDD_SERVO_IN-Pad9)") (class "Default")
      (node (ref "CON1") (pin "9") (pinfunction "VDD_SERVO_IN_9") (pintype "bidirectional"))
    )
    (net (code "152") (name "unconnected-(CON1-~{EXTERN_CS}-Pad5)") (class "Default")
      (node (ref "CON1") (pin "5") (pinfunction "~{EXTERN_CS}_5") (pintype "bidirectional"))
    )
    (net (code "153") (name "unconnected-(CON1-~{IO-LED_SAFET_PROT}-Pad28)") (class "Default")
      (node (ref "CON1") (pin "28") (pinfunction "~{IO-LED_SAFET_PROT}_28") (pintype "bidirectional"))
    )
    (net (code "154") (name "unconnected-(CON1-~{VBUS_VALID}-Pad59)") (class "Default")
      (node (ref "CON1") (pin "59") (pinfunction "~{VBUS_VALID}_59") (pintype "bidirectional"))
    )
    (net (code "155") (name "unconnected-(CON1-~{VDD_5V_HIPOWER_OC}-Pad45)") (class "Default")
      (node (ref "CON1") (pin "45") (pinfunction "~{VDD_5V_HIPOWER_OC}_45") (pintype "bidirectional"))
    )
    (net (code "156") (name "unconnected-(CON1-~{VDD_5V_PERIPH_EN}-Pad27)") (class "Default")
      (node (ref "CON1") (pin "27") (pinfunction "~{VDD_5V_PERIPH_EN}_27") (pintype "bidirectional"))
    )
    (net (code "157") (name "unconnected-(CON1-~{VDD_5V_PERIPH_OC}-Pad43)") (class "Default")
      (node (ref "CON1") (pin "43") (pinfunction "~{VDD_5V_PERIPH_OC}_43") (pintype "bidirectional"))
    )
    (net (code "158") (name "unconnected-(CON1-~{VDD_BACKUP_VALID}-Pad57)") (class "Default")
      (node (ref "CON1") (pin "57") (pinfunction "~{VDD_BACKUP_VALID}_57") (pintype "bidirectional"))
    )
    (net (code "159") (name "unconnected-(CON3-Pad4)") (class "Default")
      (node (ref "CON3") (pin "4") (pinfunction "4_4") (pintype "bidirectional"))
    )
    (net (code "160") (name "unconnected-(CON3-Pad5)") (class "Default")
      (node (ref "CON3") (pin "5") (pinfunction "5_5") (pintype "bidirectional"))
    )
    (net (code "161") (name "unconnected-(CON3-Pad7)") (class "Default")
      (node (ref "CON3") (pin "7") (pinfunction "7_7") (pintype "no_connect"))
    )
    (net (code "162") (name "unconnected-(D3-C1-Pad2)") (class "Default")
      (node (ref "D3") (pin "2") (pinfunction "C1_2") (pintype "bidirectional"))
    )
    (net (code "163") (name "unconnected-(MODULE1-CTS_5-Pad2)") (class "Default")
      (node (ref "MODULE1") (pin "2") (pinfunction "CTS_5_2") (pintype "bidirectional"))
    )
    (net (code "164") (name "unconnected-(MODULE1-RX_5-Pad1)") (class "Default")
      (node (ref "MODULE1") (pin "1") (pinfunction "RX_5_1") (pintype "bidirectional"))
    )
    (net (code "165") (name "unconnected-(MODULE1-TX_5-Pad3)") (class "Default")
      (node (ref "MODULE1") (pin "3") (pinfunction "TX_5_3") (pintype "bidirectional"))
    )
    (net (code "166") (name "unconnected-(MODULE2-ANT-Pad22)") (class "Default")
      (node (ref "MODULE2") (pin "22") (pinfunction "ANT_22") (pintype "bidirectional"))
    )
    (net (code "167") (name "unconnected-(MODULE2-EPHY_LED3-Pad10)") (class "Default")
      (node (ref "MODULE2") (pin "10") (pinfunction "EPHY_LED3_10") (pintype "bidirectional"))
    )
    (net (code "168") (name "unconnected-(MODULE2-GPIO0-Pad30)") (class "Default")
      (node (ref "MODULE2") (pin "30") (pinfunction "GPIO0_30") (pintype "bidirectional"))
    )
    (net (code "169") (name "unconnected-(MODULE2-I2C_CLK-Pad24)") (class "Default")
      (node (ref "MODULE2") (pin "24") (pinfunction "I2C_CLK_24") (pintype "bidirectional"))
    )
    (net (code "170") (name "unconnected-(MODULE2-I2C_SD-Pad25)") (class "Default")
      (node (ref "MODULE2") (pin "25") (pinfunction "I2C_SD_25") (pintype "bidirectional"))
    )
    (net (code "171") (name "unconnected-(MODULE2-I2S_CLK-Pad20)") (class "Default")
      (node (ref "MODULE2") (pin "20") (pinfunction "I2S_CLK_20") (pintype "bidirectional"))
    )
    (net (code "172") (name "unconnected-(MODULE2-I2S_SDI-Pad17)") (class "Default")
      (node (ref "MODULE2") (pin "17") (pinfunction "I2S_SDI_17") (pintype "bidirectional"))
    )
    (net (code "173") (name "unconnected-(MODULE2-I2S_SDO-Pad18)") (class "Default")
      (node (ref "MODULE2") (pin "18") (pinfunction "I2S_SDO_18") (pintype "bidirectional"))
    )
    (net (code "174") (name "unconnected-(MODULE2-I2S_WS-Pad19)") (class "Default")
      (node (ref "MODULE2") (pin "19") (pinfunction "I2S_WS_19") (pintype "bidirectional"))
    )
    (net (code "175") (name "unconnected-(MODULE2-MDI_RN_P3-Pad49)") (class "Default")
      (node (ref "MODULE2") (pin "49") (pinfunction "MDI_RN_P3_49") (pintype "bidirectional"))
    )
    (net (code "176") (name "unconnected-(MODULE2-MDI_RP_P3-Pad48)") (class "Default")
      (node (ref "MODULE2") (pin "48") (pinfunction "MDI_RP_P3_48") (pintype "bidirectional"))
    )
    (net (code "177") (name "unconnected-(MODULE2-MDI_TN_P3-Pad47)") (class "Default")
      (node (ref "MODULE2") (pin "47") (pinfunction "MDI_TN_P3_47") (pintype "bidirectional"))
    )
    (net (code "178") (name "unconnected-(MODULE2-MDI_TP_P3-Pad46)") (class "Default")
      (node (ref "MODULE2") (pin "46") (pinfunction "MDI_TP_P3_46") (pintype "bidirectional"))
    )
    (net (code "179") (name "unconnected-(MODULE2-PERST_N-Pad7)") (class "Default")
      (node (ref "MODULE2") (pin "7") (pinfunction "PERST_N_7") (pintype "bidirectional"))
    )
    (net (code "180") (name "unconnected-(MODULE2-PORST_N-Pad14)") (class "Default")
      (node (ref "MODULE2") (pin "14") (pinfunction "PORST_N_14") (pintype "bidirectional"))
    )
    (net (code "181") (name "unconnected-(MODULE2-REF_CLKO-Pad6)") (class "Default")
      (node (ref "MODULE2") (pin "6") (pinfunction "REF_CLKO_6") (pintype "bidirectional"))
    )
    (net (code "182") (name "unconnected-(MODULE2-SPI_CLK-Pad27)") (class "Default")
      (node (ref "MODULE2") (pin "27") (pinfunction "SPI_CLK_27") (pintype "bidirectional"))
    )
    (net (code "183") (name "unconnected-(MODULE2-SPI_CS1-Pad26)") (class "Default")
      (node (ref "MODULE2") (pin "26") (pinfunction "SPI_CS1_26") (pintype "bidirectional"))
    )
    (net (code "184") (name "unconnected-(MODULE2-SPI_CSO-Pad5)") (class "Default")
      (node (ref "MODULE2") (pin "5") (pinfunction "SPI_CSO_5") (pintype "bidirectional"))
    )
    (net (code "185") (name "unconnected-(MODULE2-SPI_MISO-Pad28)") (class "Default")
      (node (ref "MODULE2") (pin "28") (pinfunction "SPI_MISO_28") (pintype "bidirectional"))
    )
    (net (code "186") (name "unconnected-(MODULE2-SPI_MOSI-Pad29)") (class "Default")
      (node (ref "MODULE2") (pin "29") (pinfunction "SPI_MOSI_29") (pintype "bidirectional"))
    )
    (net (code "187") (name "unconnected-(MODULE2-WDT_RST_N-Pad8)") (class "Default")
      (node (ref "MODULE2") (pin "8") (pinfunction "WDT_RST_N_8") (pintype "bidirectional"))
    )
    (net (code "188") (name "unconnected-(MODULE2-WLED_N-Pad33)") (class "Default")
      (node (ref "MODULE2") (pin "33") (pinfunction "WLED_N_33") (pintype "bidirectional"))
    )
    (net (code "189") (name "unconnected-(T1-Pad2)") (class "Default")
      (node (ref "T1") (pin "2") (pinfunction "2_2") (pintype "bidirectional"))
    )
    (net (code "190") (name "unconnected-(T1-Pad7)") (class "Default")
      (node (ref "T1") (pin "7") (pinfunction "7_7") (pintype "bidirectional"))
    )
    (net (code "191") (name "unconnected-(T1-Pad10)") (class "Default")
      (node (ref "T1") (pin "10") (pinfunction "10_10") (pintype "bidirectional"))
    )
    (net (code "192") (name "unconnected-(T1-Pad15)") (class "Default")
      (node (ref "T1") (pin "15") (pinfunction "15_15") (pintype "bidirectional"))
    )
    (net (code "193") (name "unconnected-(T2-Pad2)") (class "Default")
      (node (ref "T2") (pin "2") (pinfunction "2_2") (pintype "bidirectional"))
    )
    (net (code "194") (name "unconnected-(T2-Pad7)") (class "Default")
      (node (ref "T2") (pin "7") (pinfunction "7_7") (pintype "bidirectional"))
    )
    (net (code "195") (name "unconnected-(T2-Pad10)") (class "Default")
      (node (ref "T2") (pin "10") (pinfunction "10_10") (pintype "bidirectional"))
    )
    (net (code "196") (name "unconnected-(T2-Pad15)") (class "Default")
      (node (ref "T2") (pin "15") (pinfunction "15_15") (pintype "bidirectional"))
    )
    (net (code "197") (name "unconnected-(T3-Pad2)") (class "Default")
      (node (ref "T3") (pin "2") (pinfunction "2_2") (pintype "bidirectional"))
    )
    (net (code "198") (name "unconnected-(T3-Pad7)") (class "Default")
      (node (ref "T3") (pin "7") (pinfunction "7_7") (pintype "bidirectional"))
    )
    (net (code "199") (name "unconnected-(T3-Pad10)") (class "Default")
      (node (ref "T3") (pin "10") (pinfunction "10_10") (pintype "bidirectional"))
    )
    (net (code "200") (name "unconnected-(T3-Pad15)") (class "Default")
      (node (ref "T3") (pin "15") (pinfunction "15_15") (pintype "bidirectional"))
    )
    (net (code "201") (name "unconnected-(T4-Pad2)") (class "Default")
      (node (ref "T4") (pin "2") (pinfunction "2_2") (pintype "bidirectional"))
    )
    (net (code "202") (name "unconnected-(T4-Pad7)") (class "Default")
      (node (ref "T4") (pin "7") (pinfunction "7_7") (pintype "bidirectional"))
    )
    (net (code "203") (name "unconnected-(T4-Pad10)") (class "Default")
      (node (ref "T4") (pin "10") (pinfunction "10_10") (pintype "bidirectional"))
    )
    (net (code "204") (name "unconnected-(T4-Pad15)") (class "Default")
      (node (ref "T4") (pin "15") (pinfunction "15_15") (pintype "bidirectional"))
    )
  )
)
